# main_board.net
KiCad netlist of a schematic drawn in EAGLE
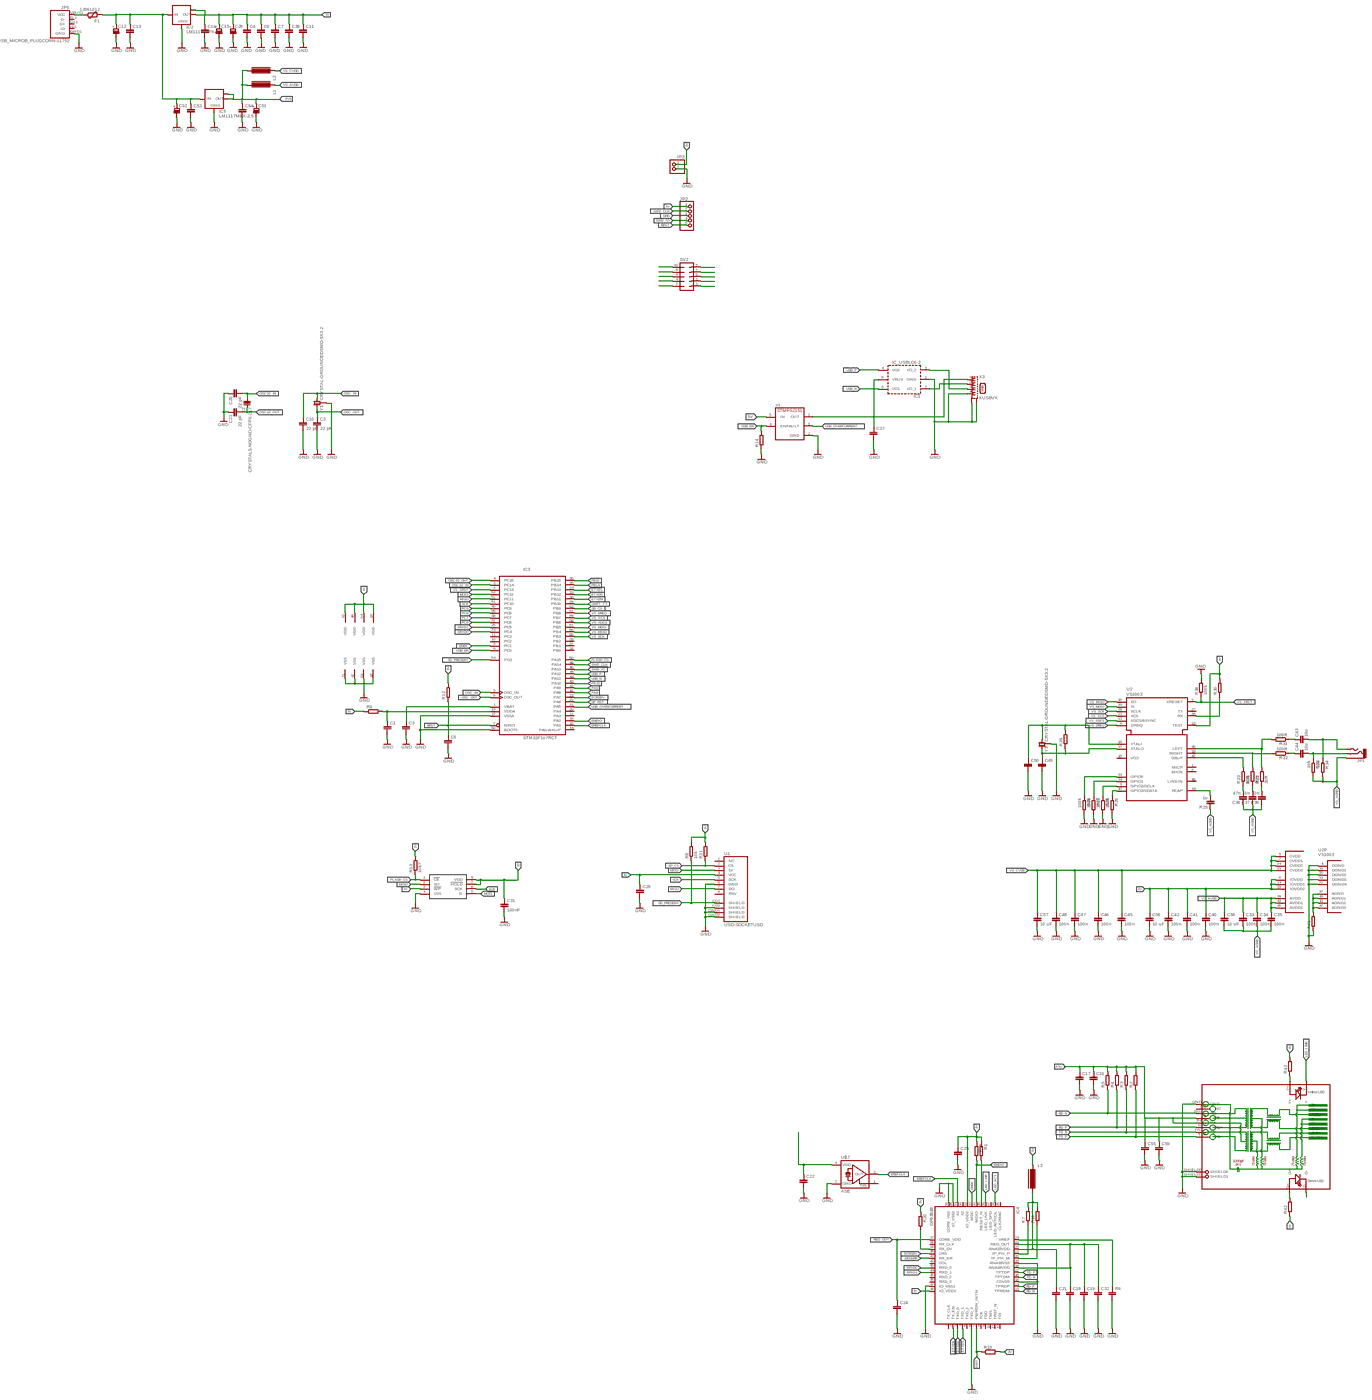
[diagram p0: schematic, sheet 1, overview]
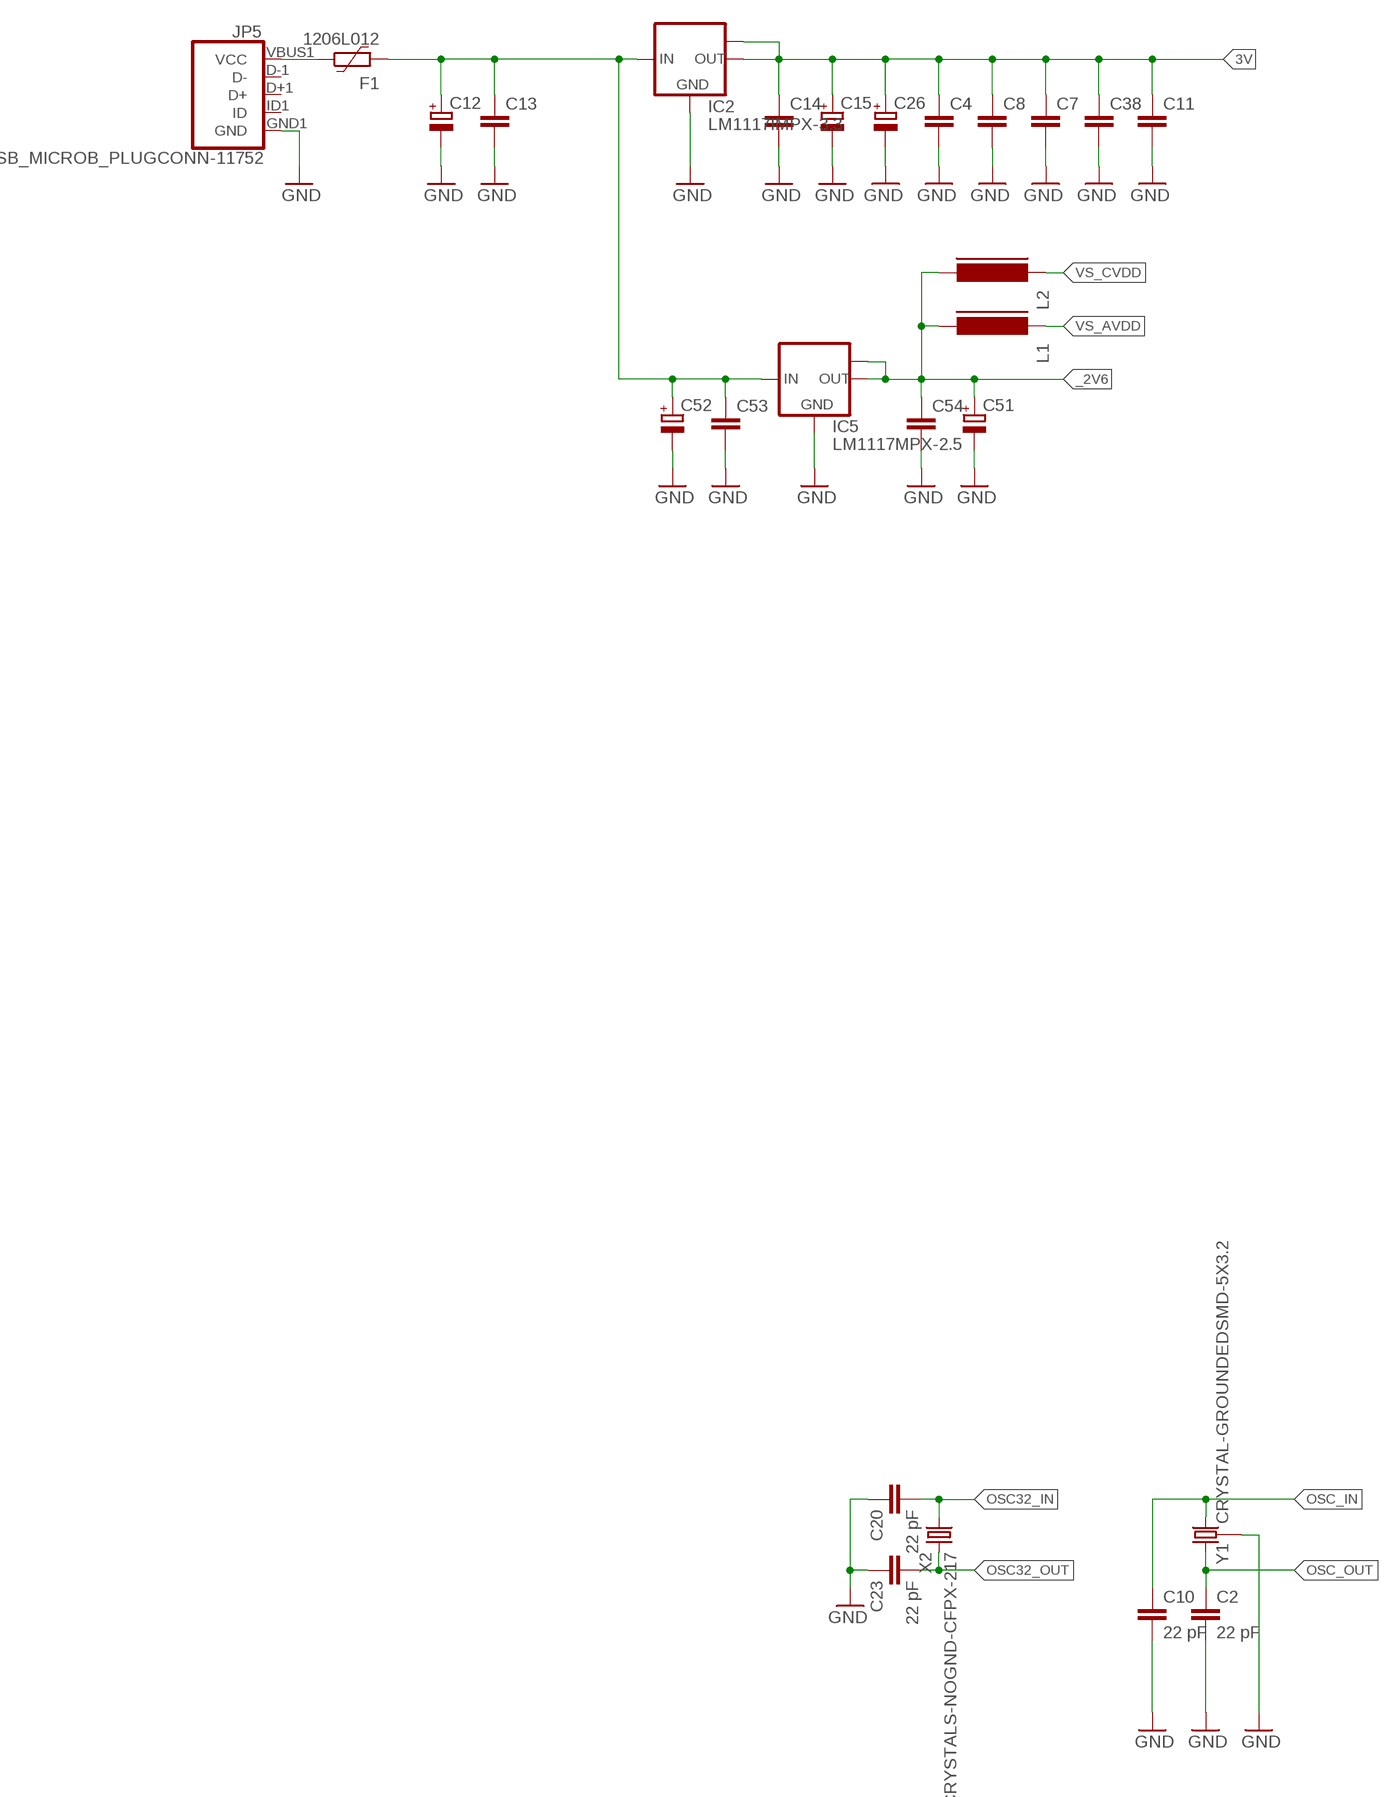
[diagram p1: schematic, sheet 1, part 1 of 4]
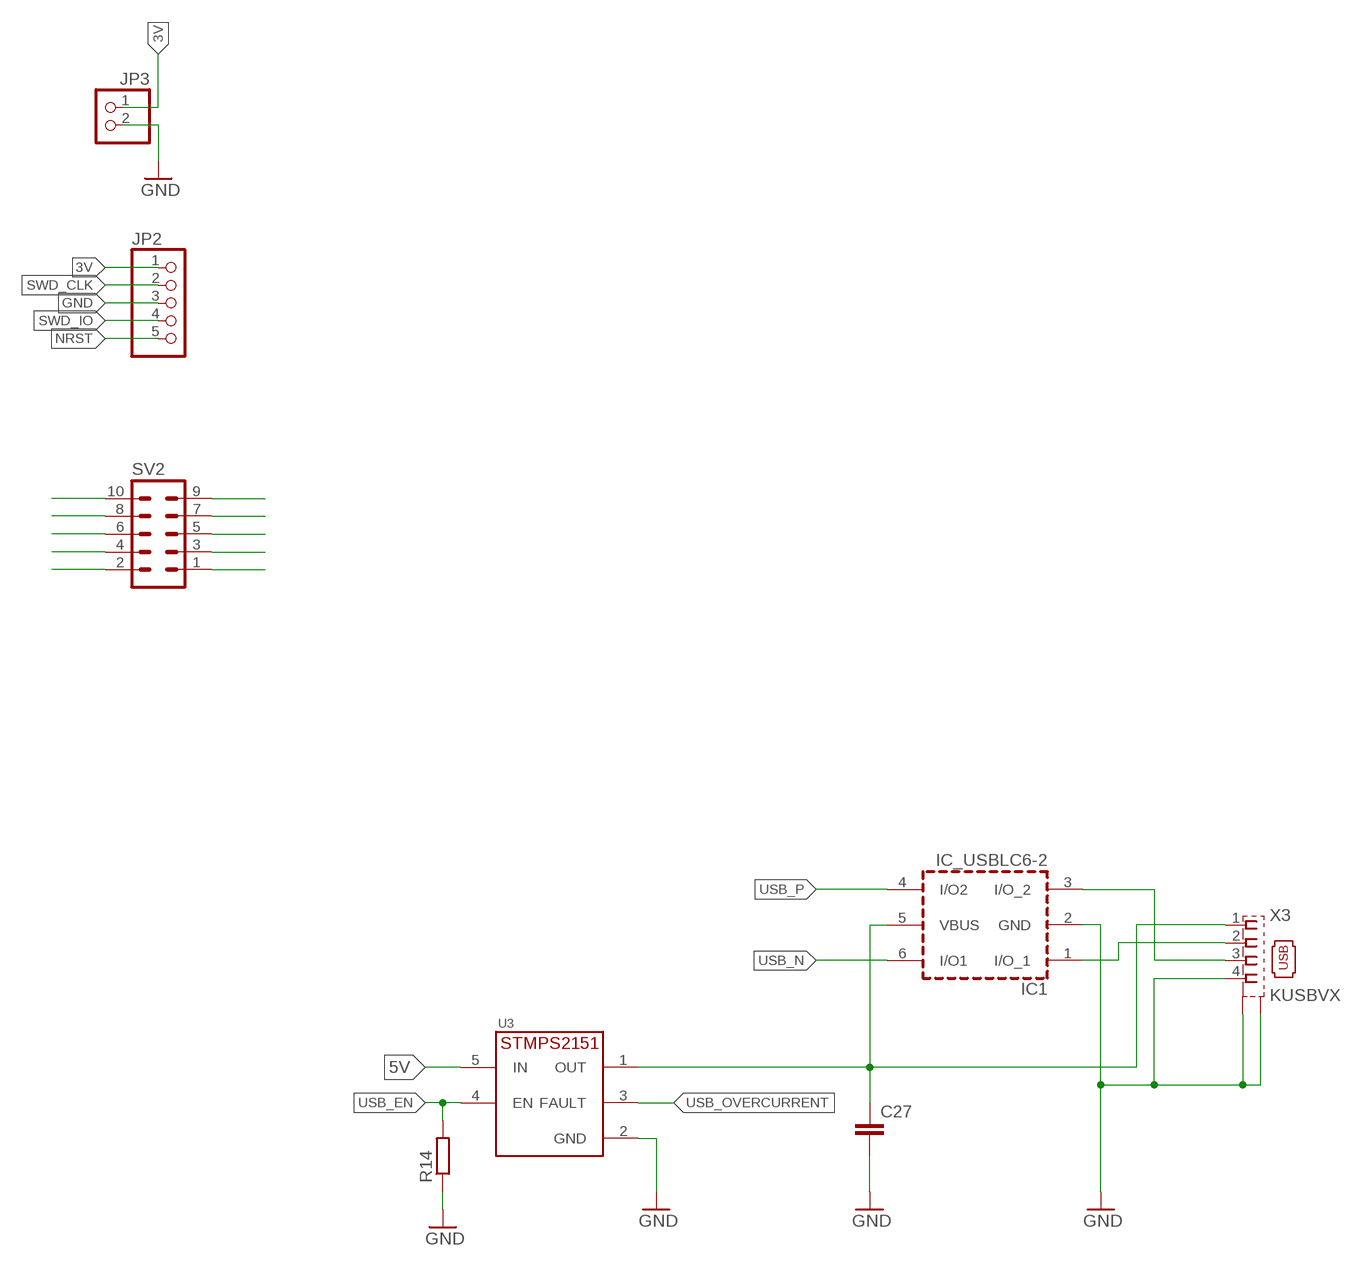
[diagram p2: schematic, sheet 1, part 2 of 4]
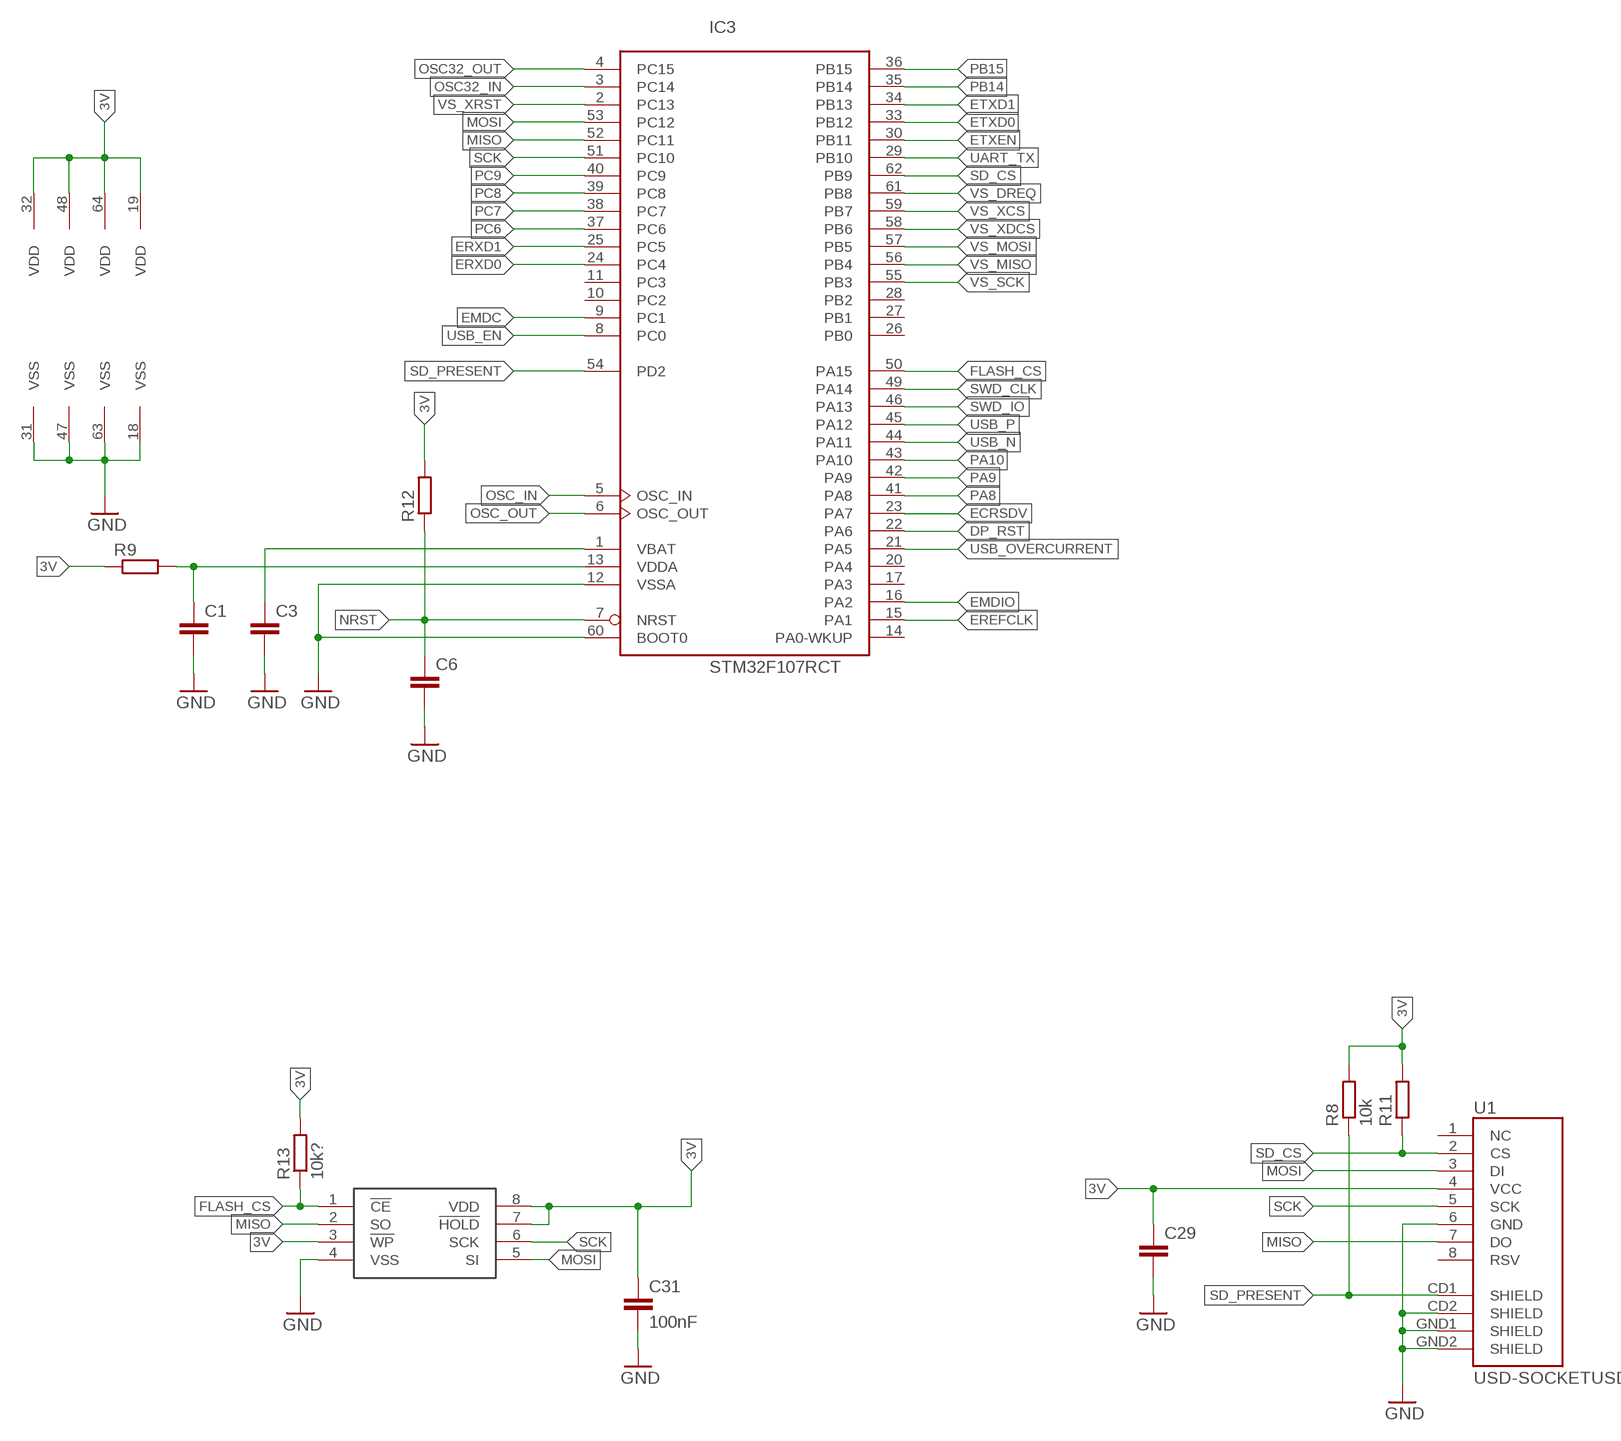
[diagram p3: schematic, sheet 1, part 3 of 4]
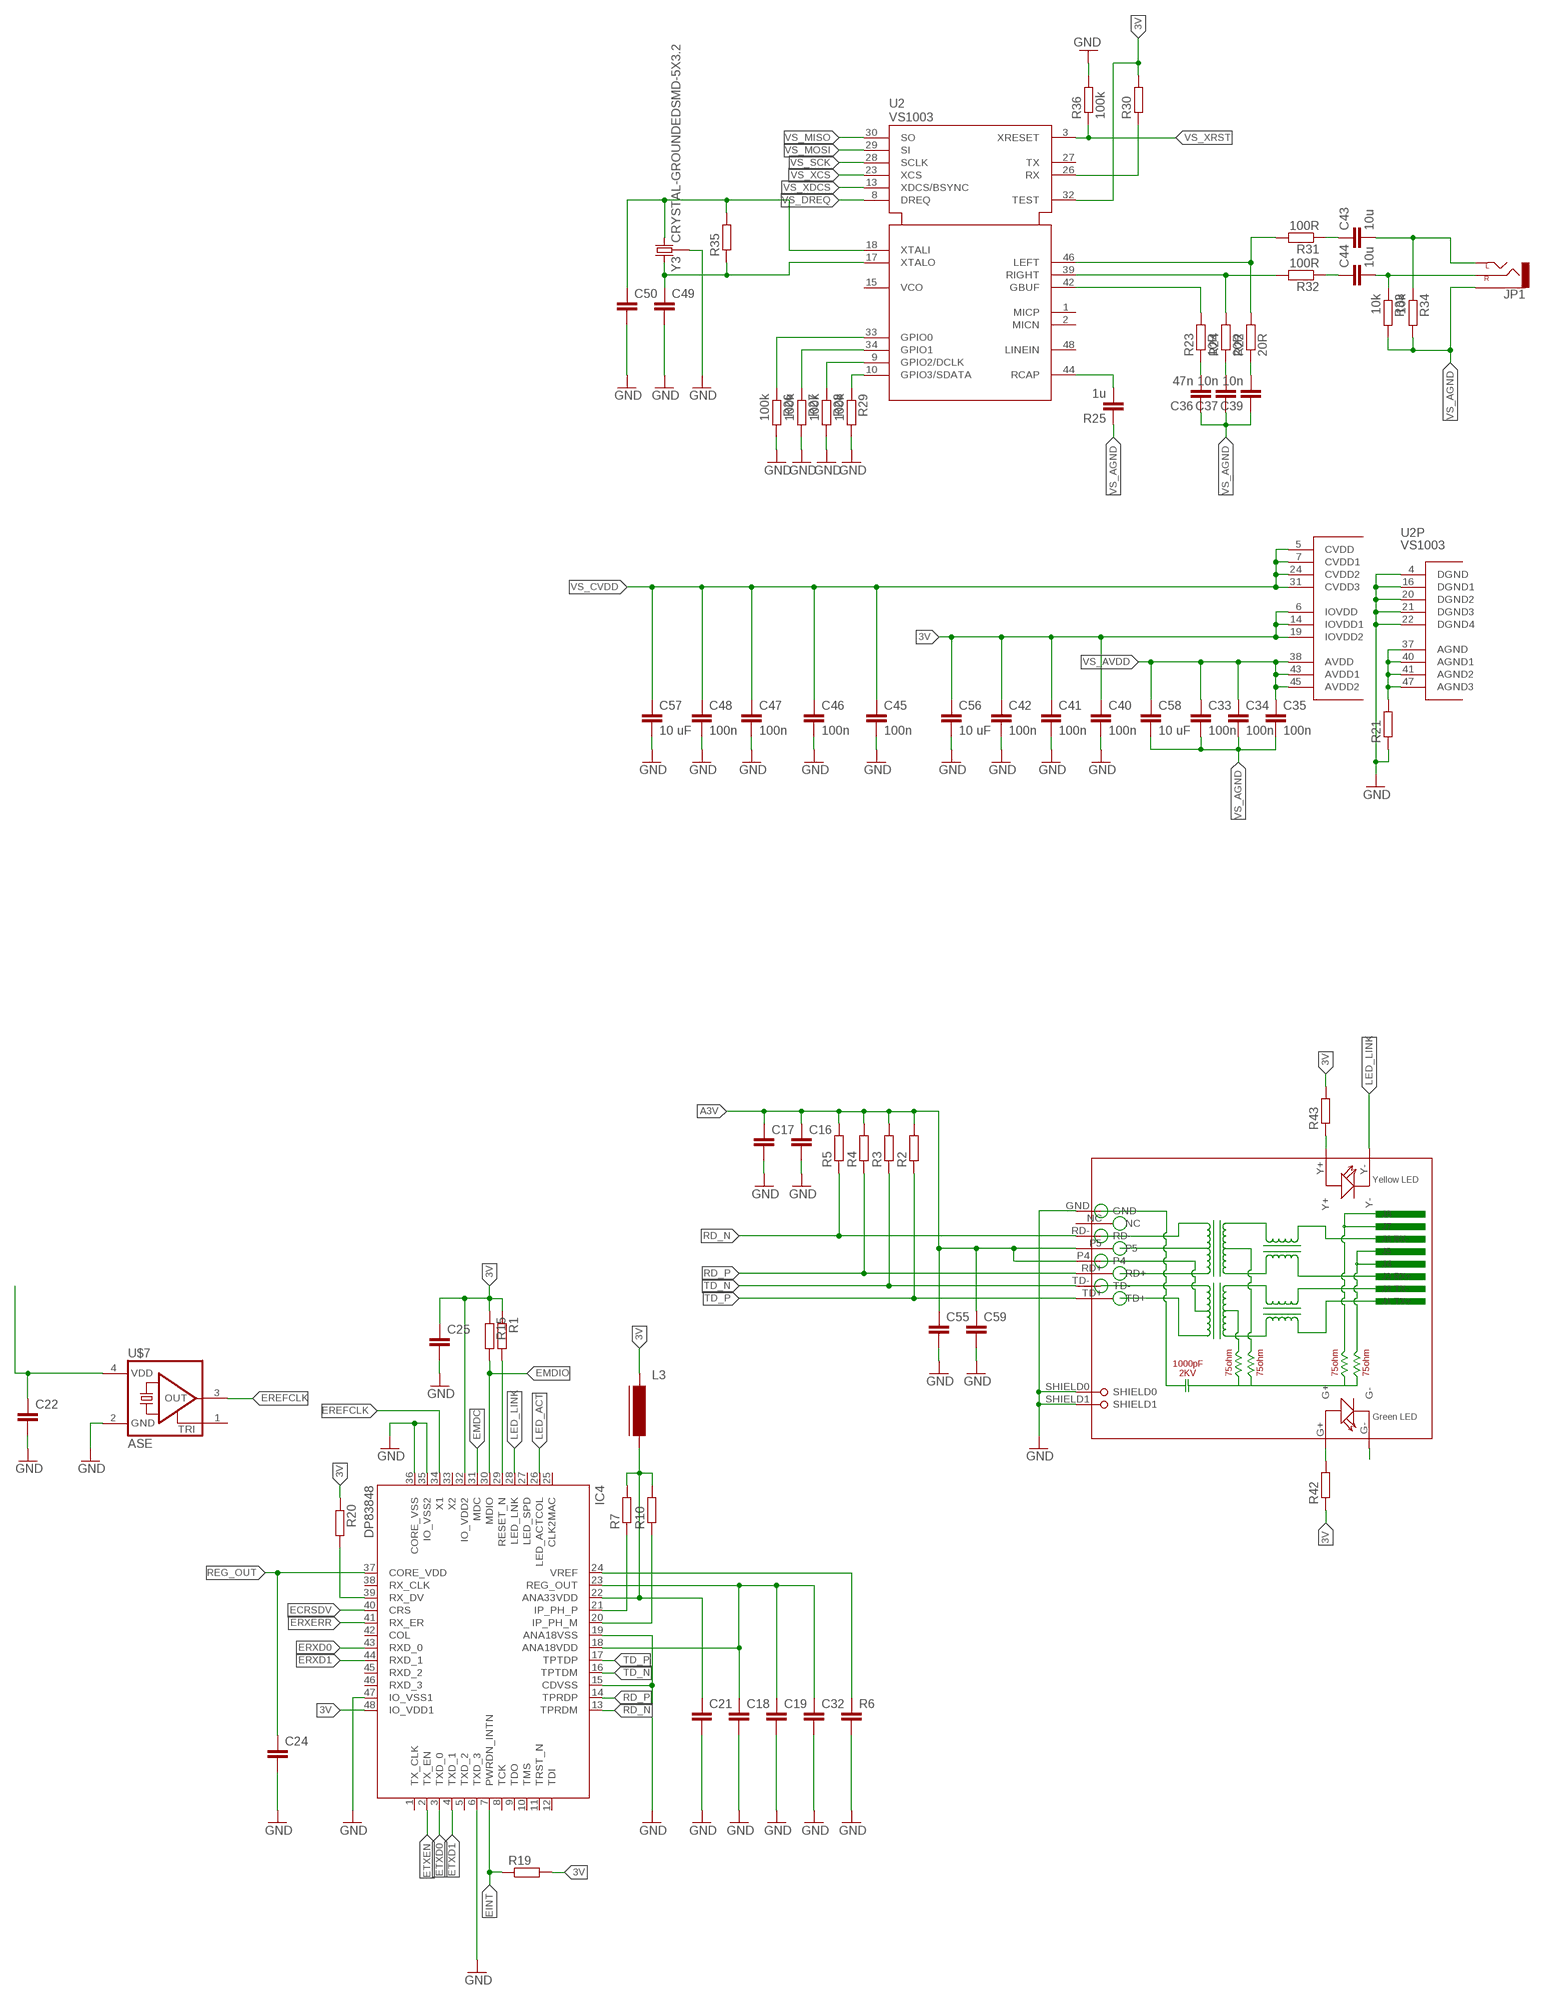
[diagram p4: schematic, sheet 1, part 4 of 4]

(export (version "E")
  (design (tool "Eeschema 10.0.6"))
  (components
    (comp (ref "C1")
      (value "C-EUC0402")
      (footprint "eagle-import:C0402")
      (libsource (lib "eagle-import") (part "C-EUC0402"))
    )
    (comp (ref "C2")
      (value "22 pF")
      (footprint "eagle-import:C0603")
      (libsource (lib "eagle-import") (part "C-EUC0603"))
    )
    (comp (ref "C3")
      (value "C-EUC0402")
      (footprint "eagle-import:C0402")
      (libsource (lib "eagle-import") (part "C-EUC0402"))
    )
    (comp (ref "C4")
      (value "C-EUC0402")
      (footprint "eagle-import:C0402")
      (libsource (lib "eagle-import") (part "C-EUC0402"))
    )
    (comp (ref "C6")
      (value "C-EUC0603")
      (footprint "eagle-import:C0603")
      (libsource (lib "eagle-import") (part "C-EUC0603"))
    )
    (comp (ref "C7")
      (value "C-EUC0402")
      (footprint "eagle-import:C0402")
      (libsource (lib "eagle-import") (part "C-EUC0402"))
    )
    (comp (ref "C8")
      (value "C-EUC0402")
      (footprint "eagle-import:C0402")
      (libsource (lib "eagle-import") (part "C-EUC0402"))
    )
    (comp (ref "C10")
      (value "22 pF")
      (footprint "eagle-import:C0603")
      (libsource (lib "eagle-import") (part "C-EUC0603"))
    )
    (comp (ref "C11")
      (value "C-EUC0402")
      (footprint "eagle-import:C0402")
      (libsource (lib "eagle-import") (part "C-EUC0402"))
    )
    (comp (ref "C12")
      (value "CPOL-EUSMCB")
      (footprint "eagle-import:SMC_B")
      (libsource (lib "eagle-import") (part "CPOL-EUSMCB"))
    )
    (comp (ref "C13")
      (value "C-EUC0603")
      (footprint "eagle-import:C0603")
      (libsource (lib "eagle-import") (part "C-EUC0603"))
    )
    (comp (ref "C14")
      (value "C-EUC0603")
      (footprint "eagle-import:C0603")
      (libsource (lib "eagle-import") (part "C-EUC0603"))
    )
    (comp (ref "C15")
      (value "CPOL-EUSMCB")
      (footprint "eagle-import:SMC_B")
      (libsource (lib "eagle-import") (part "CPOL-EUSMCB"))
    )
    (comp (ref "C16")
      (value "C-EUC0603")
      (footprint "eagle-import:C0603")
      (libsource (lib "eagle-import") (part "C-EUC0603"))
    )
    (comp (ref "C17")
      (value "C-EUC0603")
      (footprint "eagle-import:C0603")
      (libsource (lib "eagle-import") (part "C-EUC0603"))
    )
    (comp (ref "C18")
      (value "C-EUC0402")
      (footprint "eagle-import:C0402")
      (libsource (lib "eagle-import") (part "C-EUC0402"))
    )
    (comp (ref "C19")
      (value "C-EUC0402")
      (footprint "eagle-import:C0402")
      (libsource (lib "eagle-import") (part "C-EUC0402"))
    )
    (comp (ref "C20")
      (value "22 pF")
      (footprint "eagle-import:C0603")
      (libsource (lib "eagle-import") (part "C-EUC0603"))
    )
    (comp (ref "C21")
      (value "C-EUC0402")
      (footprint "eagle-import:C0402")
      (libsource (lib "eagle-import") (part "C-EUC0402"))
    )
    (comp (ref "C22")
      (value "C-EUC0402")
      (footprint "eagle-import:C0402")
      (libsource (lib "eagle-import") (part "C-EUC0402"))
    )
    (comp (ref "C23")
      (value "22 pF")
      (footprint "eagle-import:C0603")
      (libsource (lib "eagle-import") (part "C-EUC0603"))
    )
    (comp (ref "C24")
      (value "C-EUC0603")
      (footprint "eagle-import:C0603")
      (libsource (lib "eagle-import") (part "C-EUC0603"))
    )
    (comp (ref "C25")
      (value "C-EUC0603")
      (footprint "eagle-import:C0603")
      (libsource (lib "eagle-import") (part "C-EUC0603"))
    )
    (comp (ref "C26")
      (value "CPOL-EUSMCA")
      (footprint "eagle-import:SMC_A")
      (libsource (lib "eagle-import") (part "CPOL-EUSMCA"))
    )
    (comp (ref "C27")
      (value "C-EUC0603")
      (footprint "eagle-import:C0603")
      (libsource (lib "eagle-import") (part "C-EUC0603"))
    )
    (comp (ref "C29")
      (value "C-EUC0603")
      (footprint "eagle-import:C0603")
      (libsource (lib "eagle-import") (part "C-EUC0603"))
    )
    (comp (ref "C31")
      (value "100nF")
      (footprint "eagle-import:C0603")
      (libsource (lib "eagle-import") (part "C-EUC0603"))
    )
    (comp (ref "C32")
      (value "C-EUC0603")
      (footprint "eagle-import:C0603")
      (libsource (lib "eagle-import") (part "C-EUC0603"))
    )
    (comp (ref "C33")
      (value "100n")
      (footprint "eagle-import:C0603")
      (libsource (lib "eagle-import") (part "C-EUC0603"))
    )
    (comp (ref "C34")
      (value "100n")
      (footprint "eagle-import:C0603")
      (libsource (lib "eagle-import") (part "C-EUC0603"))
    )
    (comp (ref "C35")
      (value "100n")
      (footprint "eagle-import:C0603")
      (libsource (lib "eagle-import") (part "C-EUC0603"))
    )
    (comp (ref "C36")
      (value "47n")
      (footprint "eagle-import:C0603")
      (libsource (lib "eagle-import") (part "C-EUC0603"))
    )
    (comp (ref "C37")
      (value "10n")
      (footprint "eagle-import:C0603")
      (libsource (lib "eagle-import") (part "C-EUC0603"))
    )
    (comp (ref "C38")
      (value "C-EUC0402")
      (footprint "eagle-import:C0402")
      (libsource (lib "eagle-import") (part "C-EUC0402"))
    )
    (comp (ref "C39")
      (value "10n")
      (footprint "eagle-import:C0603")
      (libsource (lib "eagle-import") (part "C-EUC0603"))
    )
    (comp (ref "C40")
      (value "100n")
      (footprint "eagle-import:C0402")
      (libsource (lib "eagle-import") (part "C-EUC0402"))
    )
    (comp (ref "C41")
      (value "100n")
      (footprint "eagle-import:C0402")
      (libsource (lib "eagle-import") (part "C-EUC0402"))
    )
    (comp (ref "C42")
      (value "100n")
      (footprint "eagle-import:C0402")
      (libsource (lib "eagle-import") (part "C-EUC0402"))
    )
    (comp (ref "C43")
      (value "10u")
      (footprint "eagle-import:C0603")
      (libsource (lib "eagle-import") (part "C-EUC0603"))
    )
    (comp (ref "C44")
      (value "10u")
      (footprint "eagle-import:C0603")
      (libsource (lib "eagle-import") (part "C-EUC0603"))
    )
    (comp (ref "C45")
      (value "100n")
      (footprint "eagle-import:C0402")
      (libsource (lib "eagle-import") (part "C-EUC0402"))
    )
    (comp (ref "C46")
      (value "100n")
      (footprint "eagle-import:C0603")
      (libsource (lib "eagle-import") (part "C-EUC0603"))
    )
    (comp (ref "C47")
      (value "100n")
      (footprint "eagle-import:C0603")
      (libsource (lib "eagle-import") (part "C-EUC0603"))
    )
    (comp (ref "C48")
      (value "100n")
      (footprint "eagle-import:C0603")
      (libsource (lib "eagle-import") (part "C-EUC0603"))
    )
    (comp (ref "C49")
      (value "C-EUC0603")
      (footprint "eagle-import:C0603")
      (libsource (lib "eagle-import") (part "C-EUC0603"))
    )
    (comp (ref "C50")
      (value "C-EUC0603")
      (footprint "eagle-import:C0603")
      (libsource (lib "eagle-import") (part "C-EUC0603"))
    )
    (comp (ref "C51")
      (value "CPOL-EUSMCB")
      (footprint "eagle-import:SMC_B")
      (libsource (lib "eagle-import") (part "CPOL-EUSMCB"))
    )
    (comp (ref "C52")
      (value "CPOL-EUSMCB")
      (footprint "eagle-import:SMC_B")
      (libsource (lib "eagle-import") (part "CPOL-EUSMCB"))
    )
    (comp (ref "C53")
      (value "C-EUC1206")
      (footprint "eagle-import:C1206")
      (libsource (lib "eagle-import") (part "C-EUC1206"))
    )
    (comp (ref "C54")
      (value "C-EUC1206")
      (footprint "eagle-import:C1206")
      (libsource (lib "eagle-import") (part "C-EUC1206"))
    )
    (comp (ref "C55")
      (value "C-EUC0603")
      (footprint "eagle-import:C0603")
      (libsource (lib "eagle-import") (part "C-EUC0603"))
    )
    (comp (ref "C56")
      (value "10 uF")
      (footprint "eagle-import:C0603")
      (libsource (lib "eagle-import") (part "C-EUC0603"))
    )
    (comp (ref "C57")
      (value "10 uF")
      (footprint "eagle-import:C0603")
      (libsource (lib "eagle-import") (part "C-EUC0603"))
    )
    (comp (ref "C58")
      (value "10 uF")
      (footprint "eagle-import:C0603")
      (libsource (lib "eagle-import") (part "C-EUC0603"))
    )
    (comp (ref "C59")
      (value "C-EUC0603")
      (footprint "eagle-import:C0603")
      (libsource (lib "eagle-import") (part "C-EUC0603"))
    )
    (comp (ref "F1")
      (value "1206L012")
      (footprint "eagle-import:1206L")
      (fields (field (name "MF") "Littelfuse"))
      (libsource (lib "eagle-import") (part "?1206L012"))
    )
    (comp (ref "IC1")
      (value "IC_USBLC6-2")
      (footprint "eagle-import:SOT-23-6L")
      (libsource (lib "eagle-import") (part "IC_USBLC6-2"))
    )
    (comp (ref "IC2")
      (value "LM1117IMPX-3.3")
      (footprint "eagle-import:SOT223")
      (libsource (lib "eagle-import") (part "LM1117IMPX-3.3"))
    )
    (comp (ref "IC3")
      (value "STM32F107RCT")
      (footprint "eagle-import:LQFP64")
      (libsource (lib "eagle-import") (part "STM32F107RTC"))
    )
    (comp (ref "IC4")
      (value "DP83848")
      (footprint "eagle-import:LQFP48")
      (fields (field (name "MPN") "DP83848VYB"))
      (libsource (lib "eagle-import") (part "DP83848"))
    )
    (comp (ref "IC5")
      (value "LM1117MPX-2.5")
      (footprint "eagle-import:SOT223")
      (libsource (lib "eagle-import") (part "LM1117MPX-2.5"))
    )
    (comp (ref "JP1")
      (value "AUDIO-JACKAUDIO_JACK2")
      (footprint "eagle-import:AUDIO-JACK2")
      (libsource (lib "eagle-import") (part "AUDIO-JACKAUDIO_JACK2"))
    )
    (comp (ref "JP2")
      (value "PINHD-1X5")
      (footprint "eagle-import:1X05")
      (libsource (lib "eagle-import") (part "PINHD-1X5"))
    )
    (comp (ref "JP3")
      (value "PINHD-1X2/90")
      (footprint "eagle-import:1X02_90")
      (libsource (lib "eagle-import") (part "PINHD-1X2/90"))
    )
    (comp (ref "JP5")
      (value "USB_MICROB_PLUGCONN-11752")
      (footprint "eagle-import:USB-B-MICRO-SMD_V03")
      (libsource (lib "eagle-import") (part "USB_MICROB_PLUGCONN-11752"))
    )
    (comp (ref "L1")
      (value "FERRITE-0805")
      (footprint "eagle-import:FB805")
      (libsource (lib "eagle-import") (part "FERRITE-0805"))
    )
    (comp (ref "L2")
      (value "FERRITE-0805")
      (footprint "eagle-import:FB805")
      (libsource (lib "eagle-import") (part "FERRITE-0805"))
    )
    (comp (ref "L3")
      (value "FERRITE-0805")
      (footprint "eagle-import:FB805")
      (libsource (lib "eagle-import") (part "FERRITE-0805"))
    )
    (comp (ref "R1")
      (value "R-EU_R0402")
      (footprint "eagle-import:R0402")
      (libsource (lib "eagle-import") (part "R-EU_R0402"))
    )
    (comp (ref "R2")
      (value "R-EU_R0603")
      (footprint "eagle-import:R0603")
      (libsource (lib "eagle-import") (part "R-EU_R0603"))
    )
    (comp (ref "R3")
      (value "R-EU_R0603")
      (footprint "eagle-import:R0603")
      (libsource (lib "eagle-import") (part "R-EU_R0603"))
    )
    (comp (ref "R4")
      (value "R-EU_R0603")
      (footprint "eagle-import:R0603")
      (libsource (lib "eagle-import") (part "R-EU_R0603"))
    )
    (comp (ref "R5")
      (value "R-EU_R0603")
      (footprint "eagle-import:R0603")
      (libsource (lib "eagle-import") (part "R-EU_R0603"))
    )
    (comp (ref "R6")
      (value "C-EUC0603")
      (footprint "eagle-import:C0603")
      (libsource (lib "eagle-import") (part "C-EUC0603"))
    )
    (comp (ref "R7")
      (value "R-EU_R0402")
      (footprint "eagle-import:R0402")
      (libsource (lib "eagle-import") (part "R-EU_R0402"))
    )
    (comp (ref "R8")
      (value "10k")
      (footprint "eagle-import:R0603")
      (libsource (lib "eagle-import") (part "R-EU_R0603"))
    )
    (comp (ref "R9")
      (value "R-EU_M0805")
      (footprint "eagle-import:M0805")
      (libsource (lib "eagle-import") (part "R-EU_M0805"))
    )
    (comp (ref "R10")
      (value "R-EU_R0402")
      (footprint "eagle-import:R0402")
      (libsource (lib "eagle-import") (part "R-EU_R0402"))
    )
    (comp (ref "R11")
      (value "R-EU_R0603")
      (footprint "eagle-import:R0603")
      (libsource (lib "eagle-import") (part "R-EU_R0603"))
    )
    (comp (ref "R12")
      (value "R-EU_R0603")
      (footprint "eagle-import:R0603")
      (libsource (lib "eagle-import") (part "R-EU_R0603"))
    )
    (comp (ref "R13")
      (value "10k?")
      (footprint "eagle-import:R0603")
      (libsource (lib "eagle-import") (part "R-EU_R0603"))
    )
    (comp (ref "R14")
      (value "R-EU_R0603")
      (footprint "eagle-import:R0603")
      (libsource (lib "eagle-import") (part "R-EU_R0603"))
    )
    (comp (ref "R15")
      (value "R-EU_R0603")
      (footprint "eagle-import:R0603")
      (libsource (lib "eagle-import") (part "R-EU_R0603"))
    )
    (comp (ref "R19")
      (value "R-EU_R0402")
      (footprint "eagle-import:R0402")
      (libsource (lib "eagle-import") (part "R-EU_R0402"))
    )
    (comp (ref "R20")
      (value "R-EU_R0603")
      (footprint "eagle-import:R0603")
      (libsource (lib "eagle-import") (part "R-EU_R0603"))
    )
    (comp (ref "R21")
      (value "R-EU_R0603")
      (footprint "eagle-import:R0603")
      (libsource (lib "eagle-import") (part "R-EU_R0603"))
    )
    (comp (ref "R22")
      (value "20R")
      (footprint "eagle-import:R0603")
      (libsource (lib "eagle-import") (part "R-EU_R0603"))
    )
    (comp (ref "R23")
      (value "10R")
      (footprint "eagle-import:R0603")
      (libsource (lib "eagle-import") (part "R-EU_R0603"))
    )
    (comp (ref "R24")
      (value "20R")
      (footprint "eagle-import:R0603")
      (libsource (lib "eagle-import") (part "R-EU_R0603"))
    )
    (comp (ref "R25")
      (value "1u")
      (footprint "eagle-import:C0603")
      (libsource (lib "eagle-import") (part "C-EUC0603"))
    )
    (comp (ref "R26")
      (value "100k")
      (footprint "eagle-import:R0402")
      (libsource (lib "eagle-import") (part "R-EU_R0402"))
    )
    (comp (ref "R27")
      (value "100k")
      (footprint "eagle-import:R0402")
      (libsource (lib "eagle-import") (part "R-EU_R0402"))
    )
    (comp (ref "R28")
      (value "100k")
      (footprint "eagle-import:R0402")
      (libsource (lib "eagle-import") (part "R-EU_R0402"))
    )
    (comp (ref "R29")
      (value "100k")
      (footprint "eagle-import:R0402")
      (libsource (lib "eagle-import") (part "R-EU_R0402"))
    )
    (comp (ref "R30")
      (value "R-EU_0204/7")
      (footprint "eagle-import:0204_7")
      (libsource (lib "eagle-import") (part "R-EU_0204/7"))
    )
    (comp (ref "R31")
      (value "100R")
      (footprint "eagle-import:R0603")
      (libsource (lib "eagle-import") (part "R-EU_R0603"))
    )
    (comp (ref "R32")
      (value "100R")
      (footprint "eagle-import:R0603")
      (libsource (lib "eagle-import") (part "R-EU_R0603"))
    )
    (comp (ref "R33")
      (value "10k")
      (footprint "eagle-import:R0603")
      (libsource (lib "eagle-import") (part "R-EU_R0603"))
    )
    (comp (ref "R34")
      (value "10k")
      (footprint "eagle-import:R0603")
      (libsource (lib "eagle-import") (part "R-EU_R0603"))
    )
    (comp (ref "R35")
      (value "R-EU_R0603")
      (footprint "eagle-import:R0603")
      (libsource (lib "eagle-import") (part "R-EU_R0603"))
    )
    (comp (ref "R36")
      (value "100k")
      (footprint "eagle-import:R0603")
      (libsource (lib "eagle-import") (part "R-EU_R0603"))
    )
    (comp (ref "R42")
      (value "R-EU_R0603")
      (footprint "eagle-import:R0603")
      (libsource (lib "eagle-import") (part "R-EU_R0603"))
    )
    (comp (ref "R43")
      (value "R-EU_R0603")
      (footprint "eagle-import:R0603")
      (libsource (lib "eagle-import") (part "R-EU_R0603"))
    )
    (comp (ref "RJ1")
      (value "HR911105A")
      (footprint "eagle-import:HR911105A")
      (libsource (lib "eagle-import") (part "HR911105A"))
    )
    (comp (ref "SV2")
      (value "ML10L")
      (footprint "eagle-import:ML10L")
      (libsource (lib "eagle-import") (part "ML10L"))
    )
    (comp (ref "U$2")
      (value "SST25VF016BSO8M")
      (footprint "eagle-import:SO-08M")
      (libsource (lib "eagle-import") (part "SST25VF016BSO8M"))
    )
    (comp (ref "U$7")
      (value "ASE")
      (footprint "eagle-import:ASE")
      (libsource (lib "eagle-import") (part "ASE"))
    )
    (comp (ref "U1")
      (value "USD-SOCKETUSD")
      (footprint "eagle-import:USD-SOCKET-PP")
      (libsource (lib "eagle-import") (part "USD-SOCKETUSD"))
    )
    (comp (ref "U2")
      (value "VS1003")
      (footprint "eagle-import:LQFP48")
      (libsource (lib "eagle-import") (part "VS1003"))
    )
    (comp (ref "U3")
      (value "STMPS2151STR")
      (footprint "eagle-import:SOT-23-5L")
      (libsource (lib "eagle-import") (part "STMPS2151STR"))
    )
    (comp (ref "X2")
      (value "CRYSTALS-NOGND-CFPX-217")
      (footprint "eagle-import:3.2X1.5-2-PAD")
      (libsource (lib "eagle-import") (part "CRYSTALS-NOGND-CFPX-217"))
    )
    (comp (ref "X3")
      (value "KUSBVX")
      (footprint "eagle-import:KUSBVX")
      (libsource (lib "eagle-import") (part "KUSBVX"))
    )
    (comp (ref "Y1")
      (value "CRYSTAL-GROUNDEDSMD-5X3.2")
      (footprint "eagle-import:CRYSTAL-SMD-5X3.2-4PAD")
      (libsource (lib "eagle-import") (part "CRYSTAL-GROUNDEDSMD-5X3.2"))
    )
    (comp (ref "Y3")
      (value "CRYSTAL-GROUNDEDSMD-5X3.2")
      (footprint "eagle-import:CRYSTAL-SMD-5X3.2-4PAD")
      (libsource (lib "eagle-import") (part "CRYSTAL-GROUNDEDSMD-5X3.2"))
    )
  )
  (nets
    (net (code "1") (name "3V") (class "Default")
      (node (ref "C11") (pin "1") (pinfunction "1_1") (pintype "passive"))
      (node (ref "C14") (pin "1") (pinfunction "1_1") (pintype "passive"))
      (node (ref "C15") (pin "+") (pinfunction "+_+") (pintype "passive"))
      (node (ref "C22") (pin "1") (pinfunction "1_1") (pintype "passive"))
      (node (ref "C25") (pin "1") (pinfunction "1_1") (pintype "passive"))
      (node (ref "C26") (pin "+") (pinfunction "+_+") (pintype "passive"))
      (node (ref "C29") (pin "1") (pinfunction "1_1") (pintype "passive"))
      (node (ref "C31") (pin "1") (pinfunction "1_1") (pintype "passive"))
      (node (ref "C38") (pin "1") (pinfunction "1_1") (pintype "passive"))
      (node (ref "C4") (pin "1") (pinfunction "1_1") (pintype "passive"))
      (node (ref "C40") (pin "1") (pinfunction "1_1") (pintype "passive"))
      (node (ref "C41") (pin "1") (pinfunction "1_1") (pintype "passive"))
      (node (ref "C42") (pin "1") (pinfunction "1_1") (pintype "passive"))
      (node (ref "C56") (pin "1") (pinfunction "1_1") (pintype "passive"))
      (node (ref "C7") (pin "1") (pinfunction "1_1") (pintype "passive"))
      (node (ref "C8") (pin "1") (pinfunction "1_1") (pintype "passive"))
      (node (ref "IC2") (pin "2") (pinfunction "OUT_2") (pintype "passive"))
      (node (ref "IC2") (pin "TAB") (pinfunction "OUT1_TAB") (pintype "passive"))
      (node (ref "IC3") (pin "19") (pinfunction "VDD_19") (pintype "power_in"))
      (node (ref "IC3") (pin "32") (pinfunction "VDD_32") (pintype "power_in"))
      (node (ref "IC3") (pin "48") (pinfunction "VDD_48") (pintype "power_in"))
      (node (ref "IC3") (pin "64") (pinfunction "VDD_64") (pintype "power_in"))
      (node (ref "IC4") (pin "32") (pinfunction "IO_VDD2_32") (pintype "power_in"))
      (node (ref "IC4") (pin "48") (pinfunction "IO_VDD1_48") (pintype "power_in"))
      (node (ref "JP2") (pin "1") (pinfunction "1_1") (pintype "passive"))
      (node (ref "JP3") (pin "1") (pinfunction "1_1") (pintype "passive"))
      (node (ref "L3") (pin "1") (pinfunction "1_1") (pintype "passive"))
      (node (ref "R1") (pin "1") (pinfunction "1_1") (pintype "passive"))
      (node (ref "R11") (pin "2") (pinfunction "2_2") (pintype "passive"))
      (node (ref "R12") (pin "2") (pinfunction "2_2") (pintype "passive"))
      (node (ref "R13") (pin "2") (pinfunction "2_2") (pintype "passive"))
      (node (ref "R15") (pin "1") (pinfunction "1_1") (pintype "passive"))
      (node (ref "R19") (pin "2") (pinfunction "2_2") (pintype "passive"))
      (node (ref "R20") (pin "1") (pinfunction "1_1") (pintype "passive"))
      (node (ref "R30") (pin "2") (pinfunction "2_2") (pintype "passive"))
      (node (ref "R42") (pin "1") (pinfunction "1_1") (pintype "passive"))
      (node (ref "R43") (pin "2") (pinfunction "2_2") (pintype "passive"))
      (node (ref "R8") (pin "2") (pinfunction "2_2") (pintype "passive"))
      (node (ref "R9") (pin "1") (pinfunction "1_1") (pintype "passive"))
      (node (ref "U$2") (pin "3") (pinfunction "~{WP}_3") (pintype "bidirectional"))
      (node (ref "U$2") (pin "7") (pinfunction "~{HOLD}_7") (pintype "bidirectional"))
      (node (ref "U$2") (pin "8") (pinfunction "VDD_8") (pintype "bidirectional"))
      (node (ref "U$7") (pin "4") (pinfunction "VDD_4") (pintype "power_in"))
      (node (ref "U1") (pin "4") (pinfunction "VCC_4") (pintype "bidirectional"))
      (node (ref "U2") (pin "14") (pinfunction "IOVDD1_14") (pintype "power_in"))
      (node (ref "U2") (pin "19") (pinfunction "IOVDD2_19") (pintype "power_in"))
      (node (ref "U2") (pin "32") (pinfunction "TEST_32") (pintype "bidirectional"))
      (node (ref "U2") (pin "6") (pinfunction "IOVDD_6") (pintype "power_in"))
    )
    (net (code "2") (name "5V") (class "Default")
      (node (ref "C12") (pin "+") (pinfunction "+_+") (pintype "passive"))
      (node (ref "C13") (pin "1") (pinfunction "1_1") (pintype "passive"))
      (node (ref "C52") (pin "+") (pinfunction "+_+") (pintype "passive"))
      (node (ref "C53") (pin "1") (pinfunction "1_1") (pintype "passive"))
      (node (ref "F1") (pin "2") (pinfunction "2_2") (pintype "passive"))
      (node (ref "IC2") (pin "3") (pinfunction "IN_3") (pintype "input"))
      (node (ref "IC5") (pin "3") (pinfunction "IN_3") (pintype "input"))
      (node (ref "U3") (pin "5") (pinfunction "IN_5") (pintype "bidirectional"))
    )
    (net (code "3") (name "A3V") (class "Default")
      (node (ref "C16") (pin "1") (pinfunction "1_1") (pintype "passive"))
      (node (ref "C17") (pin "1") (pinfunction "1_1") (pintype "passive"))
      (node (ref "C21") (pin "1") (pinfunction "1_1") (pintype "passive"))
      (node (ref "C55") (pin "1") (pinfunction "1_1") (pintype "passive"))
      (node (ref "C59") (pin "1") (pinfunction "1_1") (pintype "passive"))
      (node (ref "IC4") (pin "22") (pinfunction "ANA33VDD_22") (pintype "power_in"))
      (node (ref "L3") (pin "2") (pinfunction "2_2") (pintype "passive"))
      (node (ref "R10") (pin "2") (pinfunction "2_2") (pintype "passive"))
      (node (ref "R2") (pin "2") (pinfunction "2_2") (pintype "passive"))
      (node (ref "R3") (pin "2") (pinfunction "2_2") (pintype "passive"))
      (node (ref "R4") (pin "2") (pinfunction "2_2") (pintype "passive"))
      (node (ref "R5") (pin "2") (pinfunction "2_2") (pintype "passive"))
      (node (ref "R7") (pin "2") (pinfunction "2_2") (pintype "passive"))
      (node (ref "RJ1") (pin "P4") (pinfunction "P4_P4") (pintype "bidirectional"))
      (node (ref "RJ1") (pin "P5") (pinfunction "P5_P5") (pintype "bidirectional"))
    )
    (net (code "4") (name "DP_RST") (class "Default")
      (node (ref "IC3") (pin "22") (pinfunction "PA6_22") (pintype "bidirectional"))
      (node (ref "IC4") (pin "29") (pinfunction "RESET_N_29") (pintype "input"))
      (node (ref "R1") (pin "2") (pinfunction "2_2") (pintype "passive"))
    )
    (net (code "5") (name "ECRSDV") (class "Default")
      (node (ref "IC3") (pin "23") (pinfunction "PA7_23") (pintype "bidirectional"))
      (node (ref "IC4") (pin "40") (pinfunction "CRS_40") (pintype "bidirectional"))
    )
    (net (code "6") (name "EINT") (class "Default")
      (node (ref "IC4") (pin "7") (pinfunction "PWRDN_INTN_7") (pintype "bidirectional"))
      (node (ref "R19") (pin "1") (pinfunction "1_1") (pintype "passive"))
    )
    (net (code "7") (name "EMDC") (class "Default")
      (node (ref "IC3") (pin "9") (pinfunction "PC1_9") (pintype "bidirectional"))
      (node (ref "IC4") (pin "31") (pinfunction "MDC_31") (pintype "input"))
    )
    (net (code "8") (name "EMDIO") (class "Default")
      (node (ref "IC3") (pin "16") (pinfunction "PA2_16") (pintype "bidirectional"))
      (node (ref "IC4") (pin "30") (pinfunction "MDIO_30") (pintype "bidirectional"))
      (node (ref "R15") (pin "2") (pinfunction "2_2") (pintype "passive"))
    )
    (net (code "9") (name "EREFCLK") (class "Default")
      (node (ref "IC3") (pin "15") (pinfunction "PA1_15") (pintype "bidirectional"))
      (node (ref "IC4") (pin "34") (pinfunction "X1_34") (pintype "input"))
      (node (ref "U$7") (pin "3") (pinfunction "OUT_3") (pintype "output"))
    )
    (net (code "10") (name "ERXD0") (class "Default")
      (node (ref "IC3") (pin "24") (pinfunction "PC4_24") (pintype "bidirectional"))
      (node (ref "IC4") (pin "43") (pinfunction "RXD_0_43") (pintype "bidirectional"))
    )
    (net (code "11") (name "ERXD1") (class "Default")
      (node (ref "IC3") (pin "25") (pinfunction "PC5_25") (pintype "bidirectional"))
      (node (ref "IC4") (pin "44") (pinfunction "RXD_1_44") (pintype "bidirectional"))
    )
    (net (code "12") (name "ERXERR") (class "Default")
      (node (ref "IC4") (pin "41") (pinfunction "RX_ER_41") (pintype "bidirectional"))
    )
    (net (code "13") (name "ETXD0") (class "Default")
      (node (ref "IC3") (pin "33") (pinfunction "PB12_33") (pintype "bidirectional"))
      (node (ref "IC4") (pin "3") (pinfunction "TXD_0_3") (pintype "bidirectional"))
    )
    (net (code "14") (name "ETXD1") (class "Default")
      (node (ref "IC3") (pin "34") (pinfunction "PB13_34") (pintype "bidirectional"))
      (node (ref "IC4") (pin "4") (pinfunction "TXD_1_4") (pintype "bidirectional"))
    )
    (net (code "15") (name "ETXEN") (class "Default")
      (node (ref "IC3") (pin "30") (pinfunction "PB11_30") (pintype "bidirectional"))
      (node (ref "IC4") (pin "2") (pinfunction "TX_EN_2") (pintype "bidirectional"))
    )
    (net (code "16") (name "FLASH_CS") (class "Default")
      (node (ref "IC3") (pin "50") (pinfunction "PA15_50") (pintype "bidirectional"))
      (node (ref "R13") (pin "1") (pinfunction "1_1") (pintype "passive"))
      (node (ref "U$2") (pin "1") (pinfunction "~{CE}_1") (pintype "bidirectional"))
    )
    (net (code "17") (name "GND") (class "Default")
      (node (ref "C1") (pin "2") (pinfunction "2_2") (pintype "passive"))
      (node (ref "C10") (pin "2") (pinfunction "2_2") (pintype "passive"))
      (node (ref "C11") (pin "2") (pinfunction "2_2") (pintype "passive"))
      (node (ref "C12") (pin "-") (pinfunction "-_-") (pintype "passive"))
      (node (ref "C13") (pin "2") (pinfunction "2_2") (pintype "passive"))
      (node (ref "C14") (pin "2") (pinfunction "2_2") (pintype "passive"))
      (node (ref "C15") (pin "-") (pinfunction "-_-") (pintype "passive"))
      (node (ref "C16") (pin "2") (pinfunction "2_2") (pintype "passive"))
      (node (ref "C17") (pin "2") (pinfunction "2_2") (pintype "passive"))
      (node (ref "C18") (pin "2") (pinfunction "2_2") (pintype "passive"))
      (node (ref "C19") (pin "2") (pinfunction "2_2") (pintype "passive"))
      (node (ref "C2") (pin "2") (pinfunction "2_2") (pintype "passive"))
      (node (ref "C20") (pin "1") (pinfunction "1_1") (pintype "passive"))
      (node (ref "C21") (pin "2") (pinfunction "2_2") (pintype "passive"))
      (node (ref "C22") (pin "2") (pinfunction "2_2") (pintype "passive"))
      (node (ref "C23") (pin "1") (pinfunction "1_1") (pintype "passive"))
      (node (ref "C24") (pin "2") (pinfunction "2_2") (pintype "passive"))
      (node (ref "C25") (pin "2") (pinfunction "2_2") (pintype "passive"))
      (node (ref "C26") (pin "-") (pinfunction "-_-") (pintype "passive"))
      (node (ref "C27") (pin "2") (pinfunction "2_2") (pintype "passive"))
      (node (ref "C29") (pin "2") (pinfunction "2_2") (pintype "passive"))
      (node (ref "C3") (pin "2") (pinfunction "2_2") (pintype "passive"))
      (node (ref "C31") (pin "2") (pinfunction "2_2") (pintype "passive"))
      (node (ref "C32") (pin "2") (pinfunction "2_2") (pintype "passive"))
      (node (ref "C38") (pin "2") (pinfunction "2_2") (pintype "passive"))
      (node (ref "C4") (pin "2") (pinfunction "2_2") (pintype "passive"))
      (node (ref "C40") (pin "2") (pinfunction "2_2") (pintype "passive"))
      (node (ref "C41") (pin "2") (pinfunction "2_2") (pintype "passive"))
      (node (ref "C42") (pin "2") (pinfunction "2_2") (pintype "passive"))
      (node (ref "C45") (pin "2") (pinfunction "2_2") (pintype "passive"))
      (node (ref "C46") (pin "2") (pinfunction "2_2") (pintype "passive"))
      (node (ref "C47") (pin "2") (pinfunction "2_2") (pintype "passive"))
      (node (ref "C48") (pin "2") (pinfunction "2_2") (pintype "passive"))
      (node (ref "C49") (pin "2") (pinfunction "2_2") (pintype "passive"))
      (node (ref "C50") (pin "2") (pinfunction "2_2") (pintype "passive"))
      (node (ref "C51") (pin "-") (pinfunction "-_-") (pintype "passive"))
      (node (ref "C52") (pin "-") (pinfunction "-_-") (pintype "passive"))
      (node (ref "C53") (pin "2") (pinfunction "2_2") (pintype "passive"))
      (node (ref "C54") (pin "2") (pinfunction "2_2") (pintype "passive"))
      (node (ref "C55") (pin "2") (pinfunction "2_2") (pintype "passive"))
      (node (ref "C56") (pin "2") (pinfunction "2_2") (pintype "passive"))
      (node (ref "C57") (pin "2") (pinfunction "2_2") (pintype "passive"))
      (node (ref "C59") (pin "2") (pinfunction "2_2") (pintype "passive"))
      (node (ref "C6") (pin "2") (pinfunction "2_2") (pintype "passive"))
      (node (ref "C7") (pin "2") (pinfunction "2_2") (pintype "passive"))
      (node (ref "C8") (pin "2") (pinfunction "2_2") (pintype "passive"))
      (node (ref "IC1") (pin "2") (pinfunction "GND_2") (pintype "bidirectional"))
      (node (ref "IC2") (pin "1") (pinfunction "GND_1") (pintype "input"))
      (node (ref "IC3") (pin "12") (pinfunction "VSSA_12") (pintype "power_in"))
      (node (ref "IC3") (pin "18") (pinfunction "VSS_18") (pintype "power_in"))
      (node (ref "IC3") (pin "31") (pinfunction "VSS_31") (pintype "power_in"))
      (node (ref "IC3") (pin "47") (pinfunction "VSS_47") (pintype "power_in"))
      (node (ref "IC3") (pin "60") (pinfunction "BOOT0_60") (pintype "input"))
      (node (ref "IC3") (pin "63") (pinfunction "VSS_63") (pintype "power_in"))
      (node (ref "IC4") (pin "15") (pinfunction "CDVSS_15") (pintype "power_in"))
      (node (ref "IC4") (pin "19") (pinfunction "ANA18VSS_19") (pintype "power_in"))
      (node (ref "IC4") (pin "35") (pinfunction "IO_VSS2_35") (pintype "power_in"))
      (node (ref "IC4") (pin "36") (pinfunction "CORE_VSS_36") (pintype "power_in"))
      (node (ref "IC4") (pin "47") (pinfunction "IO_VSS1_47") (pintype "power_in"))
      (node (ref "IC4") (pin "6") (pinfunction "TXD_3_6") (pintype "bidirectional"))
      (node (ref "IC5") (pin "1") (pinfunction "GND_1") (pintype "input"))
      (node (ref "JP2") (pin "3") (pinfunction "3_3") (pintype "passive"))
      (node (ref "JP3") (pin "2") (pinfunction "2_2") (pintype "passive"))
      (node (ref "JP5") (pin "GND1") (pinfunction "GND_GND1") (pintype "bidirectional"))
      (node (ref "R14") (pin "1") (pinfunction "1_1") (pintype "passive"))
      (node (ref "R21") (pin "1") (pinfunction "1_1") (pintype "passive"))
      (node (ref "R26") (pin "2") (pinfunction "2_2") (pintype "passive"))
      (node (ref "R27") (pin "2") (pinfunction "2_2") (pintype "passive"))
      (node (ref "R28") (pin "2") (pinfunction "2_2") (pintype "passive"))
      (node (ref "R29") (pin "2") (pinfunction "2_2") (pintype "passive"))
      (node (ref "R36") (pin "2") (pinfunction "2_2") (pintype "passive"))
      (node (ref "R6") (pin "2") (pinfunction "2_2") (pintype "passive"))
      (node (ref "RJ1") (pin "GND") (pinfunction "GND_GND") (pintype "bidirectional"))
      (node (ref "RJ1") (pin "SHIELD0") (pinfunction "SHIELD0_SHIELD0") (pintype "bidirectional"))
      (node (ref "RJ1") (pin "SHIELD1") (pinfunction "SHIELD1_SHIELD1") (pintype "bidirectional"))
      (node (ref "U$2") (pin "4") (pinfunction "VSS_4") (pintype "bidirectional"))
      (node (ref "U$7") (pin "2") (pinfunction "GND_2") (pintype "power_in"))
      (node (ref "U1") (pin "6") (pinfunction "GND_6") (pintype "bidirectional"))
      (node (ref "U1") (pin "CD2") (pinfunction "SHIELD_CD2") (pintype "bidirectional"))
      (node (ref "U1") (pin "GND1") (pinfunction "SHIELD_GND1") (pintype "bidirectional"))
      (node (ref "U1") (pin "GND2") (pinfunction "SHIELD_GND2") (pintype "bidirectional"))
      (node (ref "U2") (pin "16") (pinfunction "DGND1_16") (pintype "power_in"))
      (node (ref "U2") (pin "20") (pinfunction "DGND2_20") (pintype "power_in"))
      (node (ref "U2") (pin "21") (pinfunction "DGND3_21") (pintype "power_in"))
      (node (ref "U2") (pin "22") (pinfunction "DGND4_22") (pintype "power_in"))
      (node (ref "U2") (pin "4") (pinfunction "DGND_4") (pintype "power_in"))
      (node (ref "U3") (pin "2") (pinfunction "GND_2") (pintype "bidirectional"))
      (node (ref "X3") (pin "4") (pinfunction "4_4") (pintype "passive"))
      (node (ref "X3") (pin "M1") (pinfunction "S1_M1") (pintype "passive"))
      (node (ref "X3") (pin "M2") (pinfunction "S2_M2") (pintype "passive"))
      (node (ref "Y1") (pin "2") (pinfunction "3_2") (pintype "passive"))
      (node (ref "Y1") (pin "4") (pinfunction "3_4") (pintype "passive"))
      (node (ref "Y3") (pin "2") (pinfunction "3_2") (pintype "passive"))
      (node (ref "Y3") (pin "4") (pinfunction "3_4") (pintype "passive"))
    )
    (net (code "18") (name "LED_ACT") (class "Default")
      (node (ref "IC4") (pin "26") (pinfunction "LED_ACTCOL_26") (pintype "bidirectional"))
      (node (ref "RJ1") (pin "G-") (pinfunction "G-_G-") (pintype "bidirectional"))
    )
    (net (code "19") (name "LED_LINK") (class "Default")
      (node (ref "IC4") (pin "28") (pinfunction "LED_LNK_28") (pintype "bidirectional"))
      (node (ref "RJ1") (pin "Y-") (pinfunction "Y-_Y-") (pintype "bidirectional"))
    )
    (net (code "20") (name "MISO") (class "Default")
      (node (ref "IC3") (pin "52") (pinfunction "PC11_52") (pintype "bidirectional"))
      (node (ref "U$2") (pin "2") (pinfunction "SO_2") (pintype "bidirectional"))
      (node (ref "U1") (pin "7") (pinfunction "DO_7") (pintype "bidirectional"))
    )
    (net (code "21") (name "MOSI") (class "Default")
      (node (ref "IC3") (pin "53") (pinfunction "PC12_53") (pintype "bidirectional"))
      (node (ref "U$2") (pin "5") (pinfunction "SI_5") (pintype "bidirectional"))
      (node (ref "U1") (pin "3") (pinfunction "DI_3") (pintype "bidirectional"))
    )
    (net (code "22") (name "NRST") (class "Default")
      (node (ref "C6") (pin "1") (pinfunction "1_1") (pintype "passive"))
      (node (ref "IC3") (pin "7") (pinfunction "NRST_7") (pintype "bidirectional"))
      (node (ref "JP2") (pin "5") (pinfunction "5_5") (pintype "passive"))
      (node (ref "R12") (pin "1") (pinfunction "1_1") (pintype "passive"))
    )
    (net (code "23") (name "Net-(C36-Pad2)") (class "Default")
      (node (ref "C36") (pin "2") (pinfunction "2_2") (pintype "passive"))
      (node (ref "R23") (pin "1") (pinfunction "1_1") (pintype "passive"))
    )
    (net (code "24") (name "Net-(C37-Pad2)") (class "Default")
      (node (ref "C37") (pin "2") (pinfunction "2_2") (pintype "passive"))
      (node (ref "R24") (pin "1") (pinfunction "1_1") (pintype "passive"))
    )
    (net (code "25") (name "Net-(C39-Pad2)") (class "Default")
      (node (ref "C39") (pin "2") (pinfunction "2_2") (pintype "passive"))
      (node (ref "R22") (pin "1") (pinfunction "1_1") (pintype "passive"))
    )
    (net (code "26") (name "Net-(C43-Pad1)") (class "Default")
      (node (ref "C43") (pin "1") (pinfunction "1_1") (pintype "passive"))
      (node (ref "R31") (pin "1") (pinfunction "1_1") (pintype "passive"))
    )
    (net (code "27") (name "Net-(C44-Pad1)") (class "Default")
      (node (ref "C44") (pin "1") (pinfunction "1_1") (pintype "passive"))
      (node (ref "R32") (pin "1") (pinfunction "1_1") (pintype "passive"))
    )
    (net (code "28") (name "Net-(IC1-I{slash}O_1)") (class "Default")
      (node (ref "IC1") (pin "1") (pinfunction "I/O_1_1") (pintype "bidirectional"))
      (node (ref "X3") (pin "2") (pinfunction "2_2") (pintype "passive"))
    )
    (net (code "29") (name "Net-(IC1-I{slash}O_2)") (class "Default")
      (node (ref "IC1") (pin "3") (pinfunction "I/O_2_3") (pintype "bidirectional"))
      (node (ref "X3") (pin "3") (pinfunction "3_3") (pintype "passive"))
    )
    (net (code "30") (name "Net-(IC1-VBUS)") (class "Default")
      (node (ref "C27") (pin "1") (pinfunction "1_1") (pintype "passive"))
      (node (ref "IC1") (pin "5") (pinfunction "VBUS_5") (pintype "bidirectional"))
      (node (ref "U3") (pin "1") (pinfunction "OUT_1") (pintype "bidirectional"))
      (node (ref "X3") (pin "1") (pinfunction "1_1") (pintype "passive"))
    )
    (net (code "31") (name "Net-(IC3A-VBAT)") (class "Default")
      (node (ref "C3") (pin "1") (pinfunction "1_1") (pintype "passive"))
      (node (ref "IC3") (pin "1") (pinfunction "VBAT_1") (pintype "power_in"))
    )
    (net (code "32") (name "Net-(IC3A-VDDA)") (class "Default")
      (node (ref "C1") (pin "1") (pinfunction "1_1") (pintype "passive"))
      (node (ref "IC3") (pin "13") (pinfunction "VDDA_13") (pintype "power_in"))
      (node (ref "R9") (pin "2") (pinfunction "2_2") (pintype "passive"))
    )
    (net (code "33") (name "Net-(IC4-IP_PH_M)") (class "Default")
      (node (ref "IC4") (pin "20") (pinfunction "IP_PH_M_20") (pintype "input"))
      (node (ref "R10") (pin "1") (pinfunction "1_1") (pintype "passive"))
    )
    (net (code "34") (name "Net-(IC4-IP_PH_P)") (class "Default")
      (node (ref "IC4") (pin "21") (pinfunction "IP_PH_P_21") (pintype "input"))
      (node (ref "R7") (pin "1") (pinfunction "1_1") (pintype "passive"))
    )
    (net (code "35") (name "Net-(IC4-RX_DV)") (class "Default")
      (node (ref "IC4") (pin "39") (pinfunction "RX_DV_39") (pintype "bidirectional"))
      (node (ref "R20") (pin "2") (pinfunction "2_2") (pintype "passive"))
    )
    (net (code "36") (name "Net-(IC4-VREF)") (class "Default")
      (node (ref "IC4") (pin "24") (pinfunction "VREF_24") (pintype "bidirectional"))
      (node (ref "R6") (pin "1") (pinfunction "1_1") (pintype "passive"))
    )
    (net (code "37") (name "Net-(JP1-LEFT)") (class "Default")
      (node (ref "C43") (pin "2") (pinfunction "2_2") (pintype "passive"))
      (node (ref "JP1") (pin "TIP") (pinfunction "LEFT_TIP") (pintype "bidirectional"))
      (node (ref "R34") (pin "1") (pinfunction "1_1") (pintype "passive"))
    )
    (net (code "38") (name "Net-(JP1-RIGHT)") (class "Default")
      (node (ref "C44") (pin "2") (pinfunction "2_2") (pintype "passive"))
      (node (ref "JP1") (pin "RING") (pinfunction "RIGHT_RING") (pintype "bidirectional"))
      (node (ref "R33") (pin "1") (pinfunction "1_1") (pintype "passive"))
    )
    (net (code "39") (name "Net-(JP5-VCC)") (class "Default")
      (node (ref "F1") (pin "1") (pinfunction "1_1") (pintype "passive"))
      (node (ref "JP5") (pin "VBUS1") (pinfunction "VCC_VBUS1") (pintype "bidirectional"))
    )
    (net (code "40") (name "Net-(R42-Pad2)") (class "Default")
      (node (ref "R42") (pin "2") (pinfunction "2_2") (pintype "passive"))
      (node (ref "RJ1") (pin "G+") (pinfunction "G+_G+") (pintype "bidirectional"))
    )
    (net (code "41") (name "Net-(R43-Pad1)") (class "Default")
      (node (ref "R43") (pin "1") (pinfunction "1_1") (pintype "passive"))
      (node (ref "RJ1") (pin "Y+") (pinfunction "Y+_Y+") (pintype "bidirectional"))
    )
    (net (code "42") (name "Net-(U2A-GBUF)") (class "Default")
      (node (ref "R23") (pin "2") (pinfunction "2_2") (pintype "passive"))
      (node (ref "U2") (pin "42") (pinfunction "GBUF_42") (pintype "bidirectional"))
    )
    (net (code "43") (name "Net-(U2A-GPIO0)") (class "Default")
      (node (ref "R26") (pin "1") (pinfunction "1_1") (pintype "passive"))
      (node (ref "U2") (pin "33") (pinfunction "GPIO0_33") (pintype "bidirectional"))
    )
    (net (code "44") (name "Net-(U2A-GPIO1)") (class "Default")
      (node (ref "R27") (pin "1") (pinfunction "1_1") (pintype "passive"))
      (node (ref "U2") (pin "34") (pinfunction "GPIO1_34") (pintype "bidirectional"))
    )
    (net (code "45") (name "Net-(U2A-GPIO2{slash}DCLK)") (class "Default")
      (node (ref "R28") (pin "1") (pinfunction "1_1") (pintype "passive"))
      (node (ref "U2") (pin "9") (pinfunction "GPIO2/DCLK_9") (pintype "bidirectional"))
    )
    (net (code "46") (name "Net-(U2A-GPIO3{slash}SDATA)") (class "Default")
      (node (ref "R29") (pin "1") (pinfunction "1_1") (pintype "passive"))
      (node (ref "U2") (pin "10") (pinfunction "GPIO3/SDATA_10") (pintype "bidirectional"))
    )
    (net (code "47") (name "Net-(U2A-LEFT)") (class "Default")
      (node (ref "R22") (pin "2") (pinfunction "2_2") (pintype "passive"))
      (node (ref "R31") (pin "2") (pinfunction "2_2") (pintype "passive"))
      (node (ref "U2") (pin "46") (pinfunction "LEFT_46") (pintype "bidirectional"))
    )
    (net (code "48") (name "Net-(U2A-RCAP)") (class "Default")
      (node (ref "R25") (pin "2") (pinfunction "2_2") (pintype "passive"))
      (node (ref "U2") (pin "44") (pinfunction "RCAP_44") (pintype "bidirectional"))
    )
    (net (code "49") (name "Net-(U2A-RIGHT)") (class "Default")
      (node (ref "R24") (pin "2") (pinfunction "2_2") (pintype "passive"))
      (node (ref "R32") (pin "2") (pinfunction "2_2") (pintype "passive"))
      (node (ref "U2") (pin "39") (pinfunction "RIGHT_39") (pintype "bidirectional"))
    )
    (net (code "50") (name "Net-(U2A-RX)") (class "Default")
      (node (ref "R30") (pin "1") (pinfunction "1_1") (pintype "passive"))
      (node (ref "U2") (pin "26") (pinfunction "RX_26") (pintype "bidirectional"))
    )
    (net (code "51") (name "Net-(U2A-XTALI)") (class "Default")
      (node (ref "C50") (pin "1") (pinfunction "1_1") (pintype "passive"))
      (node (ref "R35") (pin "2") (pinfunction "2_2") (pintype "passive"))
      (node (ref "U2") (pin "18") (pinfunction "XTALI_18") (pintype "bidirectional"))
      (node (ref "Y3") (pin "1") (pinfunction "2_1") (pintype "passive"))
    )
    (net (code "52") (name "Net-(U2A-XTALO)") (class "Default")
      (node (ref "C49") (pin "1") (pinfunction "1_1") (pintype "passive"))
      (node (ref "R35") (pin "1") (pinfunction "1_1") (pintype "passive"))
      (node (ref "U2") (pin "17") (pinfunction "XTALO_17") (pintype "bidirectional"))
      (node (ref "Y3") (pin "3") (pinfunction "1_3") (pintype "passive"))
    )
    (net (code "53") (name "OSC32_IN") (class "Default")
      (node (ref "C20") (pin "2") (pinfunction "2_2") (pintype "passive"))
      (node (ref "IC3") (pin "3") (pinfunction "PC14_3") (pintype "bidirectional"))
      (node (ref "X2") (pin "1") (pinfunction "1_1") (pintype "passive"))
    )
    (net (code "54") (name "OSC32_OUT") (class "Default")
      (node (ref "C23") (pin "2") (pinfunction "2_2") (pintype "passive"))
      (node (ref "IC3") (pin "4") (pinfunction "PC15_4") (pintype "bidirectional"))
      (node (ref "X2") (pin "2") (pinfunction "2_2") (pintype "passive"))
    )
    (net (code "55") (name "OSC_IN") (class "Default")
      (node (ref "C10") (pin "1") (pinfunction "1_1") (pintype "passive"))
      (node (ref "IC3") (pin "5") (pinfunction "OSC_IN_5") (pintype "bidirectional"))
      (node (ref "Y1") (pin "1") (pinfunction "2_1") (pintype "passive"))
    )
    (net (code "56") (name "OSC_OUT") (class "Default")
      (node (ref "C2") (pin "1") (pinfunction "1_1") (pintype "passive"))
      (node (ref "IC3") (pin "6") (pinfunction "OSC_OUT_6") (pintype "bidirectional"))
      (node (ref "Y1") (pin "3") (pinfunction "1_3") (pintype "passive"))
    )
    (net (code "57") (name "PA8") (class "Default")
      (node (ref "IC3") (pin "41") (pinfunction "PA8_41") (pintype "bidirectional"))
      (node (ref "SV2") (pin "8") (pinfunction "8_8") (pintype "passive"))
    )
    (net (code "58") (name "PA9") (class "Default")
      (node (ref "IC3") (pin "42") (pinfunction "PA9_42") (pintype "bidirectional"))
      (node (ref "SV2") (pin "9") (pinfunction "9_9") (pintype "passive"))
    )
    (net (code "59") (name "PA10") (class "Default")
      (node (ref "IC3") (pin "43") (pinfunction "PA10_43") (pintype "bidirectional"))
      (node (ref "SV2") (pin "10") (pinfunction "10_10") (pintype "passive"))
    )
    (net (code "60") (name "PB14") (class "Default")
      (node (ref "IC3") (pin "35") (pinfunction "PB14_35") (pintype "bidirectional"))
      (node (ref "SV2") (pin "2") (pinfunction "2_2") (pintype "passive"))
    )
    (net (code "61") (name "PB15") (class "Default")
      (node (ref "IC3") (pin "36") (pinfunction "PB15_36") (pintype "bidirectional"))
      (node (ref "SV2") (pin "3") (pinfunction "3_3") (pintype "passive"))
    )
    (net (code "62") (name "PC6") (class "Default")
      (node (ref "IC3") (pin "37") (pinfunction "PC6_37") (pintype "bidirectional"))
      (node (ref "SV2") (pin "4") (pinfunction "4_4") (pintype "passive"))
    )
    (net (code "63") (name "PC7") (class "Default")
      (node (ref "IC3") (pin "38") (pinfunction "PC7_38") (pintype "bidirectional"))
      (node (ref "SV2") (pin "5") (pinfunction "5_5") (pintype "passive"))
    )
    (net (code "64") (name "PC8") (class "Default")
      (node (ref "IC3") (pin "39") (pinfunction "PC8_39") (pintype "bidirectional"))
      (node (ref "SV2") (pin "6") (pinfunction "6_6") (pintype "passive"))
    )
    (net (code "65") (name "PC9") (class "Default")
      (node (ref "IC3") (pin "40") (pinfunction "PC9_40") (pintype "bidirectional"))
      (node (ref "SV2") (pin "7") (pinfunction "7_7") (pintype "passive"))
    )
    (net (code "66") (name "RD_N") (class "Default")
      (node (ref "IC4") (pin "13") (pinfunction "TPRDM_13") (pintype "bidirectional"))
      (node (ref "R5") (pin "1") (pinfunction "1_1") (pintype "passive"))
      (node (ref "RJ1") (pin "RD-") (pinfunction "RD-_RD-") (pintype "bidirectional"))
    )
    (net (code "67") (name "RD_P") (class "Default")
      (node (ref "IC4") (pin "14") (pinfunction "TPRDP_14") (pintype "bidirectional"))
      (node (ref "R4") (pin "1") (pinfunction "1_1") (pintype "passive"))
      (node (ref "RJ1") (pin "RD+") (pinfunction "RD+_RD+") (pintype "bidirectional"))
    )
    (net (code "68") (name "REG_OUT") (class "Default")
      (node (ref "C18") (pin "1") (pinfunction "1_1") (pintype "passive"))
      (node (ref "C19") (pin "1") (pinfunction "1_1") (pintype "passive"))
      (node (ref "C24") (pin "1") (pinfunction "1_1") (pintype "passive"))
      (node (ref "C32") (pin "1") (pinfunction "1_1") (pintype "passive"))
      (node (ref "IC4") (pin "18") (pinfunction "ANA18VDD_18") (pintype "power_in"))
      (node (ref "IC4") (pin "23") (pinfunction "REG_OUT_23") (pintype "output"))
      (node (ref "IC4") (pin "37") (pinfunction "CORE_VDD_37") (pintype "power_in"))
    )
    (net (code "69") (name "SCK") (class "Default")
      (node (ref "IC3") (pin "51") (pinfunction "PC10_51") (pintype "bidirectional"))
      (node (ref "U$2") (pin "6") (pinfunction "SCK_6") (pintype "bidirectional"))
      (node (ref "U1") (pin "5") (pinfunction "SCK_5") (pintype "bidirectional"))
    )
    (net (code "70") (name "SD_CS") (class "Default")
      (node (ref "IC3") (pin "62") (pinfunction "PB9_62") (pintype "bidirectional"))
      (node (ref "R11") (pin "1") (pinfunction "1_1") (pintype "passive"))
      (node (ref "U1") (pin "2") (pinfunction "CS_2") (pintype "bidirectional"))
    )
    (net (code "71") (name "SD_PRESENT") (class "Default")
      (node (ref "IC3") (pin "54") (pinfunction "PD2_54") (pintype "bidirectional"))
      (node (ref "R8") (pin "1") (pinfunction "1_1") (pintype "passive"))
      (node (ref "U1") (pin "CD1") (pinfunction "SHIELD_CD1") (pintype "bidirectional"))
    )
    (net (code "72") (name "SWD_CLK") (class "Default")
      (node (ref "IC3") (pin "49") (pinfunction "PA14_49") (pintype "bidirectional"))
      (node (ref "JP2") (pin "2") (pinfunction "2_2") (pintype "passive"))
    )
    (net (code "73") (name "SWD_IO") (class "Default")
      (node (ref "IC3") (pin "46") (pinfunction "PA13_46") (pintype "bidirectional"))
      (node (ref "JP2") (pin "4") (pinfunction "4_4") (pintype "passive"))
    )
    (net (code "74") (name "TD_N") (class "Default")
      (node (ref "IC4") (pin "16") (pinfunction "TPTDM_16") (pintype "bidirectional"))
      (node (ref "R3") (pin "1") (pinfunction "1_1") (pintype "passive"))
      (node (ref "RJ1") (pin "TD-") (pinfunction "TD-_TD-") (pintype "bidirectional"))
    )
    (net (code "75") (name "TD_P") (class "Default")
      (node (ref "IC4") (pin "17") (pinfunction "TPTDP_17") (pintype "bidirectional"))
      (node (ref "R2") (pin "1") (pinfunction "1_1") (pintype "passive"))
      (node (ref "RJ1") (pin "TD+") (pinfunction "TD+_TD+") (pintype "bidirectional"))
    )
    (net (code "76") (name "UART_TX") (class "Default")
      (node (ref "IC3") (pin "29") (pinfunction "PB10_29") (pintype "bidirectional"))
      (node (ref "SV2") (pin "1") (pinfunction "1_1") (pintype "passive"))
    )
    (net (code "77") (name "USB_EN") (class "Default")
      (node (ref "IC3") (pin "8") (pinfunction "PC0_8") (pintype "bidirectional"))
      (node (ref "R14") (pin "2") (pinfunction "2_2") (pintype "passive"))
      (node (ref "U3") (pin "4") (pinfunction "EN_4") (pintype "bidirectional"))
    )
    (net (code "78") (name "USB_N") (class "Default")
      (node (ref "IC1") (pin "6") (pinfunction "I/O1_6") (pintype "bidirectional"))
      (node (ref "IC3") (pin "44") (pinfunction "PA11_44") (pintype "bidirectional"))
    )
    (net (code "79") (name "USB_OVERCURRENT") (class "Default")
      (node (ref "IC3") (pin "21") (pinfunction "PA5_21") (pintype "bidirectional"))
      (node (ref "U3") (pin "3") (pinfunction "FAULT_3") (pintype "bidirectional"))
    )
    (net (code "80") (name "USB_P") (class "Default")
      (node (ref "IC1") (pin "4") (pinfunction "I/O2_4") (pintype "bidirectional"))
      (node (ref "IC3") (pin "45") (pinfunction "PA12_45") (pintype "bidirectional"))
    )
    (net (code "81") (name "VS_AGND") (class "Default")
      (node (ref "C33") (pin "2") (pinfunction "2_2") (pintype "passive"))
      (node (ref "C34") (pin "2") (pinfunction "2_2") (pintype "passive"))
      (node (ref "C35") (pin "2") (pinfunction "2_2") (pintype "passive"))
      (node (ref "C36") (pin "1") (pinfunction "1_1") (pintype "passive"))
      (node (ref "C37") (pin "1") (pinfunction "1_1") (pintype "passive"))
      (node (ref "C39") (pin "1") (pinfunction "1_1") (pintype "passive"))
      (node (ref "C58") (pin "2") (pinfunction "2_2") (pintype "passive"))
      (node (ref "JP1") (pin "SLEEVE") (pinfunction "SLEEVE_SLEEVE") (pintype "bidirectional"))
      (node (ref "R21") (pin "2") (pinfunction "2_2") (pintype "passive"))
      (node (ref "R25") (pin "1") (pinfunction "1_1") (pintype "passive"))
      (node (ref "R33") (pin "2") (pinfunction "2_2") (pintype "passive"))
      (node (ref "R34") (pin "2") (pinfunction "2_2") (pintype "passive"))
      (node (ref "U2") (pin "37") (pinfunction "AGND_37") (pintype "power_in"))
      (node (ref "U2") (pin "40") (pinfunction "AGND1_40") (pintype "power_in"))
      (node (ref "U2") (pin "41") (pinfunction "AGND2_41") (pintype "power_in"))
      (node (ref "U2") (pin "47") (pinfunction "AGND3_47") (pintype "power_in"))
    )
    (net (code "82") (name "VS_AVDD") (class "Default")
      (node (ref "C33") (pin "1") (pinfunction "1_1") (pintype "passive"))
      (node (ref "C34") (pin "1") (pinfunction "1_1") (pintype "passive"))
      (node (ref "C35") (pin "1") (pinfunction "1_1") (pintype "passive"))
      (node (ref "C58") (pin "1") (pinfunction "1_1") (pintype "passive"))
      (node (ref "L1") (pin "1") (pinfunction "1_1") (pintype "passive"))
      (node (ref "U2") (pin "38") (pinfunction "AVDD_38") (pintype "power_in"))
      (node (ref "U2") (pin "43") (pinfunction "AVDD1_43") (pintype "power_in"))
      (node (ref "U2") (pin "45") (pinfunction "AVDD2_45") (pintype "power_in"))
    )
    (net (code "83") (name "VS_CVDD") (class "Default")
      (node (ref "C45") (pin "1") (pinfunction "1_1") (pintype "passive"))
      (node (ref "C46") (pin "1") (pinfunction "1_1") (pintype "passive"))
      (node (ref "C47") (pin "1") (pinfunction "1_1") (pintype "passive"))
      (node (ref "C48") (pin "1") (pinfunction "1_1") (pintype "passive"))
      (node (ref "C57") (pin "1") (pinfunction "1_1") (pintype "passive"))
      (node (ref "L2") (pin "1") (pinfunction "1_1") (pintype "passive"))
      (node (ref "U2") (pin "24") (pinfunction "CVDD2_24") (pintype "power_in"))
      (node (ref "U2") (pin "31") (pinfunction "CVDD3_31") (pintype "power_in"))
      (node (ref "U2") (pin "5") (pinfunction "CVDD_5") (pintype "power_in"))
      (node (ref "U2") (pin "7") (pinfunction "CVDD1_7") (pintype "power_in"))
    )
    (net (code "84") (name "VS_DREQ") (class "Default")
      (node (ref "IC3") (pin "61") (pinfunction "PB8_61") (pintype "bidirectional"))
      (node (ref "U2") (pin "8") (pinfunction "DREQ_8") (pintype "bidirectional"))
    )
    (net (code "85") (name "VS_MISO") (class "Default")
      (node (ref "IC3") (pin "56") (pinfunction "PB4_56") (pintype "bidirectional"))
      (node (ref "U2") (pin "30") (pinfunction "SO_30") (pintype "bidirectional"))
    )
    (net (code "86") (name "VS_MOSI") (class "Default")
      (node (ref "IC3") (pin "57") (pinfunction "PB5_57") (pintype "bidirectional"))
      (node (ref "U2") (pin "29") (pinfunction "SI_29") (pintype "bidirectional"))
    )
    (net (code "87") (name "VS_SCK") (class "Default")
      (node (ref "IC3") (pin "55") (pinfunction "PB3_55") (pintype "bidirectional"))
      (node (ref "U2") (pin "28") (pinfunction "SCLK_28") (pintype "bidirectional"))
    )
    (net (code "88") (name "VS_XCS") (class "Default")
      (node (ref "IC3") (pin "59") (pinfunction "PB7_59") (pintype "bidirectional"))
      (node (ref "U2") (pin "23") (pinfunction "XCS_23") (pintype "bidirectional"))
    )
    (net (code "89") (name "VS_XDCS") (class "Default")
      (node (ref "IC3") (pin "58") (pinfunction "PB6_58") (pintype "bidirectional"))
      (node (ref "U2") (pin "13") (pinfunction "XDCS/BSYNC_13") (pintype "bidirectional"))
    )
    (net (code "90") (name "VS_XRST") (class "Default")
      (node (ref "IC3") (pin "2") (pinfunction "PC13_2") (pintype "bidirectional"))
      (node (ref "R36") (pin "1") (pinfunction "1_1") (pintype "passive"))
      (node (ref "U2") (pin "3") (pinfunction "XRESET_3") (pintype "bidirectional"))
    )
    (net (code "91") (name "_2V6") (class "Default")
      (node (ref "C51") (pin "+") (pinfunction "+_+") (pintype "passive"))
      (node (ref "C54") (pin "1") (pinfunction "1_1") (pintype "passive"))
      (node (ref "IC5") (pin "2") (pinfunction "OUT_2") (pintype "passive"))
      (node (ref "IC5") (pin "TAB") (pinfunction "OUT1_TAB") (pintype "passive"))
      (node (ref "L1") (pin "2") (pinfunction "2_2") (pintype "passive"))
      (node (ref "L2") (pin "2") (pinfunction "2_2") (pintype "passive"))
    )
    (net (code "92") (name "unconnected-(IC3A-PA0-WKUP-Pad14)") (class "Default")
      (node (ref "IC3") (pin "14") (pinfunction "PA0-WKUP_14") (pintype "bidirectional"))
    )
    (net (code "93") (name "unconnected-(IC3A-PA3-Pad17)") (class "Default")
      (node (ref "IC3") (pin "17") (pinfunction "PA3_17") (pintype "bidirectional"))
    )
    (net (code "94") (name "unconnected-(IC3A-PA4-Pad20)") (class "Default")
      (node (ref "IC3") (pin "20") (pinfunction "PA4_20") (pintype "bidirectional"))
    )
    (net (code "95") (name "unconnected-(IC3A-PB0-Pad26)") (class "Default")
      (node (ref "IC3") (pin "26") (pinfunction "PB0_26") (pintype "bidirectional"))
    )
    (net (code "96") (name "unconnected-(IC3A-PB1-Pad27)") (class "Default")
      (node (ref "IC3") (pin "27") (pinfunction "PB1_27") (pintype "bidirectional"))
    )
    (net (code "97") (name "unconnected-(IC3A-PB2-Pad28)") (class "Default")
      (node (ref "IC3") (pin "28") (pinfunction "PB2_28") (pintype "bidirectional"))
    )
    (net (code "98") (name "unconnected-(IC3A-PC2-Pad10)") (class "Default")
      (node (ref "IC3") (pin "10") (pinfunction "PC2_10") (pintype "bidirectional"))
    )
    (net (code "99") (name "unconnected-(IC3A-PC3-Pad11)") (class "Default")
      (node (ref "IC3") (pin "11") (pinfunction "PC3_11") (pintype "bidirectional"))
    )
    (net (code "100") (name "unconnected-(IC4-CLK2MAC-Pad25)") (class "Default")
      (node (ref "IC4") (pin "25") (pinfunction "CLK2MAC_25") (pintype "bidirectional"))
    )
    (net (code "101") (name "unconnected-(IC4-COL-Pad42)") (class "Default")
      (node (ref "IC4") (pin "42") (pinfunction "COL_42") (pintype "bidirectional"))
    )
    (net (code "102") (name "unconnected-(IC4-LED_SPD-Pad27)") (class "Default")
      (node (ref "IC4") (pin "27") (pinfunction "LED_SPD_27") (pintype "bidirectional"))
    )
    (net (code "103") (name "unconnected-(IC4-RXD_2-Pad45)") (class "Default")
      (node (ref "IC4") (pin "45") (pinfunction "RXD_2_45") (pintype "bidirectional"))
    )
    (net (code "104") (name "unconnected-(IC4-RXD_3-Pad46)") (class "Default")
      (node (ref "IC4") (pin "46") (pinfunction "RXD_3_46") (pintype "bidirectional"))
    )
    (net (code "105") (name "unconnected-(IC4-RX_CLK-Pad38)") (class "Default")
      (node (ref "IC4") (pin "38") (pinfunction "RX_CLK_38") (pintype "bidirectional"))
    )
    (net (code "106") (name "unconnected-(IC4-TCK-Pad8)") (class "Default")
      (node (ref "IC4") (pin "8") (pinfunction "TCK_8") (pintype "input"))
    )
    (net (code "107") (name "unconnected-(IC4-TDI-Pad12)") (class "Default")
      (node (ref "IC4") (pin "12") (pinfunction "TDI_12") (pintype "input"))
    )
    (net (code "108") (name "unconnected-(IC4-TDO-Pad9)") (class "Default")
      (node (ref "IC4") (pin "9") (pinfunction "TDO_9") (pintype "output"))
    )
    (net (code "109") (name "unconnected-(IC4-TMS-Pad10)") (class "Default")
      (node (ref "IC4") (pin "10") (pinfunction "TMS_10") (pintype "input"))
    )
    (net (code "110") (name "unconnected-(IC4-TRST_N-Pad11)") (class "Default")
      (node (ref "IC4") (pin "11") (pinfunction "TRST_N_11") (pintype "input"))
    )
    (net (code "111") (name "unconnected-(IC4-TXD_2-Pad5)") (class "Default")
      (node (ref "IC4") (pin "5") (pinfunction "TXD_2_5") (pintype "bidirectional"))
    )
    (net (code "112") (name "unconnected-(IC4-TX_CLK-Pad1)") (class "Default")
      (node (ref "IC4") (pin "1") (pinfunction "TX_CLK_1") (pintype "bidirectional"))
    )
    (net (code "113") (name "unconnected-(IC4-X2-Pad33)") (class "Default")
      (node (ref "IC4") (pin "33") (pinfunction "X2_33") (pintype "output"))
    )
    (net (code "114") (name "unconnected-(JP5-D+-PadD+1)") (class "Default")
      (node (ref "JP5") (pin "D+1") (pinfunction "D+_D+1") (pintype "bidirectional"))
    )
    (net (code "115") (name "unconnected-(JP5-D--PadD-1)") (class "Default")
      (node (ref "JP5") (pin "D-1") (pinfunction "D-_D-1") (pintype "bidirectional"))
    )
    (net (code "116") (name "unconnected-(JP5-ID-PadID1)") (class "Default")
      (node (ref "JP5") (pin "ID1") (pinfunction "ID_ID1") (pintype "bidirectional"))
    )
    (net (code "117") (name "unconnected-(RJ1-PadNC)") (class "Default")
      (node (ref "RJ1") (pin "NC") (pinfunction "NC_NC") (pintype "bidirectional"))
    )
    (net (code "118") (name "unconnected-(U$7-TRI-Pad1)") (class "Default")
      (node (ref "U$7") (pin "1") (pinfunction "TRI_1") (pintype "input"))
    )
    (net (code "119") (name "unconnected-(U1-NC-Pad1)") (class "Default")
      (node (ref "U1") (pin "1") (pinfunction "NC_1") (pintype "bidirectional"))
    )
    (net (code "120") (name "unconnected-(U1-RSV-Pad8)") (class "Default")
      (node (ref "U1") (pin "8") (pinfunction "RSV_8") (pintype "bidirectional"))
    )
    (net (code "121") (name "unconnected-(U2A-LINEIN-Pad48)") (class "Default")
      (node (ref "U2") (pin "48") (pinfunction "LINEIN_48") (pintype "bidirectional"))
    )
    (net (code "122") (name "unconnected-(U2A-MICN-Pad2)") (class "Default")
      (node (ref "U2") (pin "2") (pinfunction "MICN_2") (pintype "bidirectional"))
    )
    (net (code "123") (name "unconnected-(U2A-MICP-Pad1)") (class "Default")
      (node (ref "U2") (pin "1") (pinfunction "MICP_1") (pintype "bidirectional"))
    )
    (net (code "124") (name "unconnected-(U2A-TX-Pad27)") (class "Default")
      (node (ref "U2") (pin "27") (pinfunction "TX_27") (pintype "bidirectional"))
    )
    (net (code "125") (name "unconnected-(U2A-VCO-Pad15)") (class "Default")
      (node (ref "U2") (pin "15") (pinfunction "VCO_15") (pintype "bidirectional"))
    )
  )
)
